# LED_kocka.net
KiCad netlist of a schematic drawn in Altium Designer
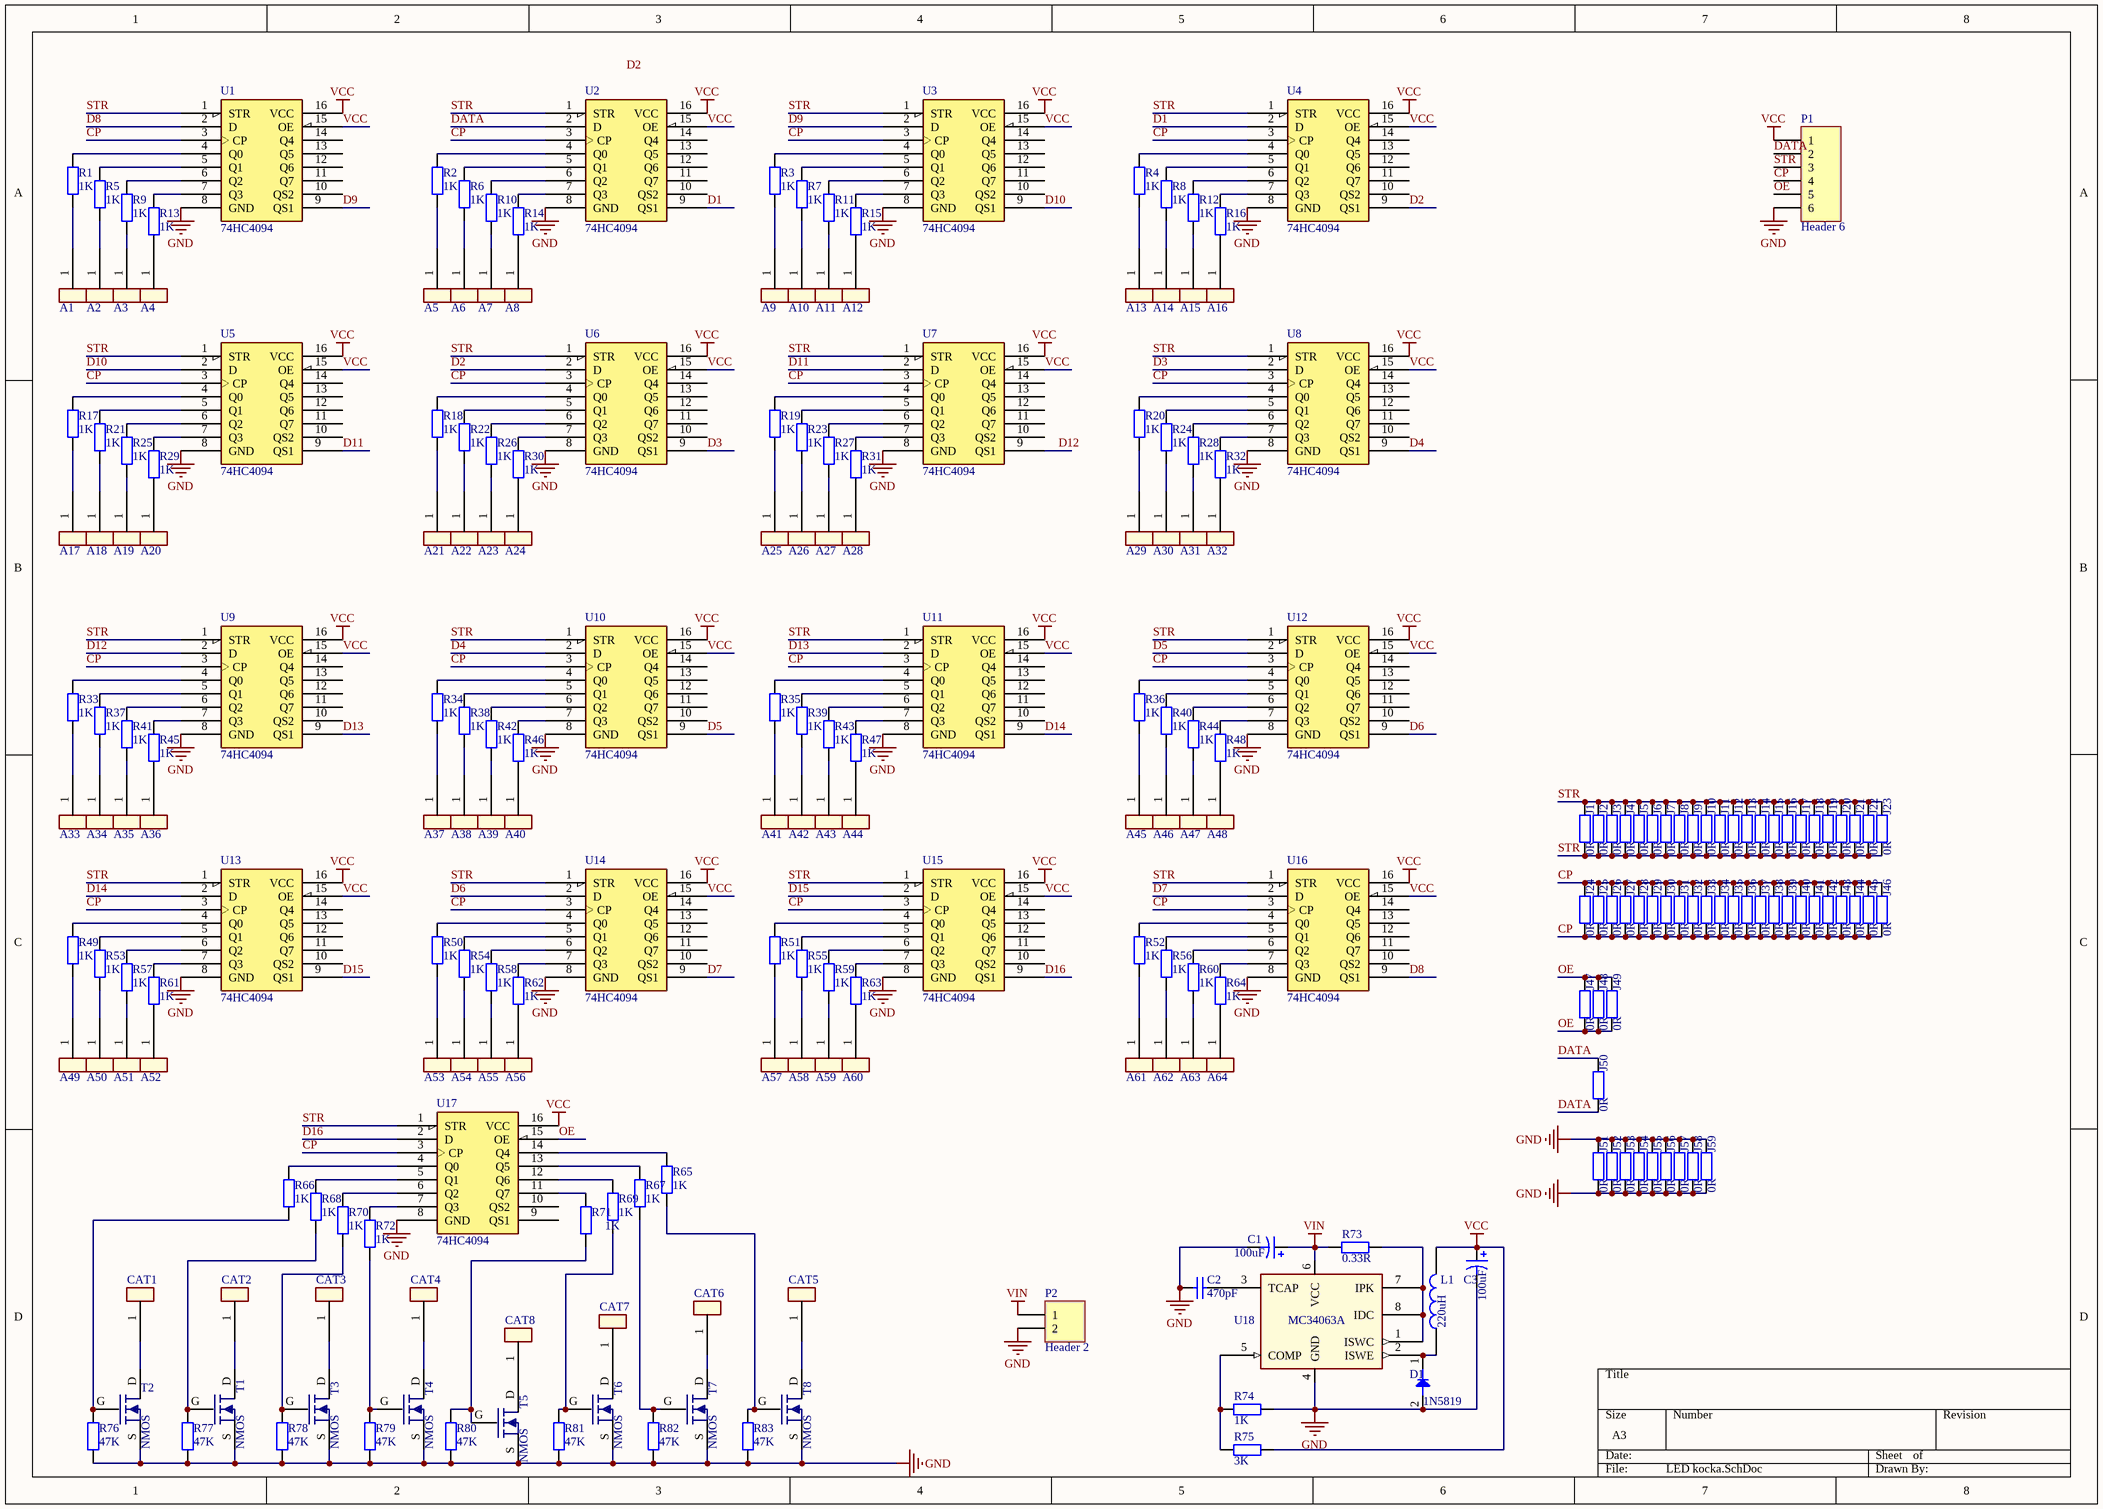
[diagram p0: LED kocka.SchDoc]

(export (version "E")
  (design (tool "Eeschema 10.0.6"))
  (components
    (comp (ref "A1") (value "~") (footprint "via_300x400") (libsource (lib "Other") (part "TestPoint")))
    (comp (ref "A2") (value "~") (footprint "via_300x400") (libsource (lib "Other") (part "TestPoint")))
    (comp (ref "A3") (value "~") (footprint "via_300x400") (libsource (lib "Other") (part "TestPoint")))
    (comp (ref "A4") (value "~") (footprint "via_300x400") (libsource (lib "Other") (part "TestPoint")))
    (comp (ref "A5") (value "~") (footprint "via_300x400") (libsource (lib "Other") (part "TestPoint")))
    (comp (ref "A6") (value "~") (footprint "via_300x400") (libsource (lib "Other") (part "TestPoint")))
    (comp (ref "A7") (value "~") (footprint "via_300x400") (libsource (lib "Other") (part "TestPoint")))
    (comp (ref "A8") (value "~") (footprint "via_300x400") (libsource (lib "Other") (part "TestPoint")))
    (comp (ref "A9") (value "~") (footprint "via_300x400") (libsource (lib "Other") (part "TestPoint")))
    (comp (ref "A10") (value "~") (footprint "via_300x400") (libsource (lib "Other") (part "TestPoint")))
    (comp (ref "A11") (value "~") (footprint "via_300x400") (libsource (lib "Other") (part "TestPoint")))
    (comp (ref "A12") (value "~") (footprint "via_300x400") (libsource (lib "Other") (part "TestPoint")))
    (comp (ref "A13") (value "~") (footprint "via_300x400") (libsource (lib "Other") (part "TestPoint")))
    (comp (ref "A14") (value "~") (footprint "via_300x400") (libsource (lib "Other") (part "TestPoint")))
    (comp (ref "A15") (value "~") (footprint "via_300x400") (libsource (lib "Other") (part "TestPoint")))
    (comp (ref "A16") (value "~") (footprint "via_300x400") (libsource (lib "Other") (part "TestPoint")))
    (comp (ref "A17") (value "~") (footprint "via_300x400") (libsource (lib "Other") (part "TestPoint")))
    (comp (ref "A18") (value "~") (footprint "via_300x400") (libsource (lib "Other") (part "TestPoint")))
    (comp (ref "A19") (value "~") (footprint "via_300x400") (libsource (lib "Other") (part "TestPoint")))
    (comp (ref "A20") (value "~") (footprint "via_300x400") (libsource (lib "Other") (part "TestPoint")))
    (comp (ref "A21") (value "~") (footprint "via_300x400") (libsource (lib "Other") (part "TestPoint")))
    (comp (ref "A22") (value "~") (footprint "via_300x400") (libsource (lib "Other") (part "TestPoint")))
    (comp (ref "A23") (value "~") (footprint "via_300x400") (libsource (lib "Other") (part "TestPoint")))
    (comp (ref "A24") (value "~") (footprint "via_300x400") (libsource (lib "Other") (part "TestPoint")))
    (comp (ref "A25") (value "~") (footprint "via_300x400") (libsource (lib "Other") (part "TestPoint")))
    (comp (ref "A26") (value "~") (footprint "via_300x400") (libsource (lib "Other") (part "TestPoint")))
    (comp (ref "A27") (value "~") (footprint "via_300x400") (libsource (lib "Other") (part "TestPoint")))
    (comp (ref "A28") (value "~") (footprint "via_300x400") (libsource (lib "Other") (part "TestPoint")))
    (comp (ref "A29") (value "~") (footprint "via_300x400") (libsource (lib "Other") (part "TestPoint")))
    (comp (ref "A30") (value "~") (footprint "via_300x400") (libsource (lib "Other") (part "TestPoint")))
    (comp (ref "A31") (value "~") (footprint "via_300x400") (libsource (lib "Other") (part "TestPoint")))
    (comp (ref "A32") (value "~") (footprint "via_300x400") (libsource (lib "Other") (part "TestPoint")))
    (comp (ref "A33") (value "~") (footprint "via_300x400") (libsource (lib "Other") (part "TestPoint")))
    (comp (ref "A34") (value "~") (footprint "via_300x400") (libsource (lib "Other") (part "TestPoint")))
    (comp (ref "A35") (value "~") (footprint "via_300x400") (libsource (lib "Other") (part "TestPoint")))
    (comp (ref "A36") (value "~") (footprint "via_300x400") (libsource (lib "Other") (part "TestPoint")))
    (comp (ref "A37") (value "~") (footprint "via_300x400") (libsource (lib "Other") (part "TestPoint")))
    (comp (ref "A38") (value "~") (footprint "via_300x400") (libsource (lib "Other") (part "TestPoint")))
    (comp (ref "A39") (value "~") (footprint "via_300x400") (libsource (lib "Other") (part "TestPoint")))
    (comp (ref "A40") (value "~") (footprint "via_300x400") (libsource (lib "Other") (part "TestPoint")))
    (comp (ref "A41") (value "~") (footprint "via_300x400") (libsource (lib "Other") (part "TestPoint")))
    (comp (ref "A42") (value "~") (footprint "via_300x400") (libsource (lib "Other") (part "TestPoint")))
    (comp (ref "A43") (value "~") (footprint "via_300x400") (libsource (lib "Other") (part "TestPoint")))
    (comp (ref "A44") (value "~") (footprint "via_300x400") (libsource (lib "Other") (part "TestPoint")))
    (comp (ref "A45") (value "~") (footprint "via_300x400") (libsource (lib "Other") (part "TestPoint")))
    (comp (ref "A46") (value "~") (footprint "via_300x400") (libsource (lib "Other") (part "TestPoint")))
    (comp (ref "A47") (value "~") (footprint "via_300x400") (libsource (lib "Other") (part "TestPoint")))
    (comp (ref "A48") (value "~") (footprint "via_300x400") (libsource (lib "Other") (part "TestPoint")))
    (comp (ref "A49") (value "~") (footprint "via_300x400") (libsource (lib "Other") (part "TestPoint")))
    (comp (ref "A50") (value "~") (footprint "via_300x400") (libsource (lib "Other") (part "TestPoint")))
    (comp (ref "A51") (value "~") (footprint "via_300x400") (libsource (lib "Other") (part "TestPoint")))
    (comp (ref "A52") (value "~") (footprint "via_300x400") (libsource (lib "Other") (part "TestPoint")))
    (comp (ref "A53") (value "~") (footprint "via_300x400") (libsource (lib "Other") (part "TestPoint")))
    (comp (ref "A54") (value "~") (footprint "via_300x400") (libsource (lib "Other") (part "TestPoint")))
    (comp (ref "A55") (value "~") (footprint "via_300x400") (libsource (lib "Other") (part "TestPoint")))
    (comp (ref "A56") (value "~") (footprint "via_300x400") (libsource (lib "Other") (part "TestPoint")))
    (comp (ref "A57") (value "~") (footprint "via_300x400") (libsource (lib "Other") (part "TestPoint")))
    (comp (ref "A58") (value "~") (footprint "via_300x400") (libsource (lib "Other") (part "TestPoint")))
    (comp (ref "A59") (value "~") (footprint "via_300x400") (libsource (lib "Other") (part "TestPoint")))
    (comp (ref "A60") (value "~") (footprint "via_300x400") (libsource (lib "Other") (part "TestPoint")))
    (comp (ref "A61") (value "~") (footprint "via_300x400") (libsource (lib "Other") (part "TestPoint")))
    (comp (ref "A62") (value "~") (footprint "via_300x400") (libsource (lib "Other") (part "TestPoint")))
    (comp (ref "A63") (value "~") (footprint "via_300x400") (libsource (lib "Other") (part "TestPoint")))
    (comp (ref "A64") (value "~") (footprint "via_300x400") (libsource (lib "Other") (part "TestPoint")))
    (comp (ref "C1")
      (value "100uF")
      (footprint "FP_CAP_ELKO_6,3X6,3")
      (description "Polarized Capacitor")
      (libsource (lib "Capacitor") (part "CAP_ELECT"))
    )
    (comp (ref "C2")
      (value "470pF")
      (footprint "FP_0805_CAP_085")
      (description "Capacitor")
      (libsource (lib "Capacitor") (part "CAP"))
    )
    (comp (ref "C3")
      (value "100uF")
      (footprint "FP_CAP_ELKO_6,3X6,3")
      (description "Polarized Capacitor")
      (libsource (lib "Capacitor") (part "CAP_ELECT"))
    )
    (comp (ref "CAT1") (value "~") (footprint "via_300x400") (libsource (lib "") (part "TestPoint_1")))
    (comp (ref "CAT2") (value "~") (footprint "via_300x400") (libsource (lib "") (part "TestPoint_1")))
    (comp (ref "CAT3") (value "~") (footprint "via_300x400") (libsource (lib "") (part "TestPoint_1")))
    (comp (ref "CAT4") (value "~") (footprint "via_300x400") (libsource (lib "") (part "TestPoint_1")))
    (comp (ref "CAT5") (value "~") (footprint "via_300x400") (libsource (lib "") (part "TestPoint_1")))
    (comp (ref "CAT6") (value "~") (footprint "via_300x400") (libsource (lib "") (part "TestPoint_1")))
    (comp (ref "CAT7") (value "~") (footprint "via_300x400") (libsource (lib "") (part "TestPoint_1")))
    (comp (ref "CAT8") (value "~") (footprint "via_300x400") (libsource (lib "") (part "TestPoint_1")))
    (comp (ref "D1") (value "1N5819") (footprint "FP_SOD-123") (libsource (lib "Diode") (part "DIODE")))
    (comp (ref "J1")
      (value "0R")
      (footprint "FP_1206_RES_SIMPLE")
      (description "Resistor")
      (libsource (lib "") (part "RES_1"))
    )
    (comp (ref "J2")
      (value "0R")
      (footprint "FP_1206_RES_SIMPLE")
      (description "Resistor")
      (libsource (lib "") (part "RES_1"))
    )
    (comp (ref "J3")
      (value "0R")
      (footprint "FP_1206_RES_SIMPLE")
      (description "Resistor")
      (libsource (lib "") (part "RES_1"))
    )
    (comp (ref "J4")
      (value "0R")
      (footprint "FP_1206_RES_SIMPLE")
      (description "Resistor")
      (libsource (lib "") (part "RES_1"))
    )
    (comp (ref "J5")
      (value "0R")
      (footprint "FP_1206_RES_SIMPLE")
      (description "Resistor")
      (libsource (lib "") (part "RES_1"))
    )
    (comp (ref "J6")
      (value "0R")
      (footprint "FP_1206_RES_SIMPLE")
      (description "Resistor")
      (libsource (lib "") (part "RES_1"))
    )
    (comp (ref "J7")
      (value "0R")
      (footprint "FP_1206_RES_SIMPLE")
      (description "Resistor")
      (libsource (lib "") (part "RES_1"))
    )
    (comp (ref "J8")
      (value "0R")
      (footprint "FP_1206_RES_SIMPLE")
      (description "Resistor")
      (libsource (lib "") (part "RES_1"))
    )
    (comp (ref "J9")
      (value "0R")
      (footprint "FP_1206_RES_SIMPLE")
      (description "Resistor")
      (libsource (lib "") (part "RES_1"))
    )
    (comp (ref "J10")
      (value "0R")
      (footprint "FP_1206_RES_SIMPLE")
      (description "Resistor")
      (libsource (lib "") (part "RES_1"))
    )
    (comp (ref "J11")
      (value "0R")
      (footprint "FP_1206_RES_SIMPLE")
      (description "Resistor")
      (libsource (lib "") (part "RES_1"))
    )
    (comp (ref "J12")
      (value "0R")
      (footprint "FP_1206_RES_SIMPLE")
      (description "Resistor")
      (libsource (lib "") (part "RES_1"))
    )
    (comp (ref "J13")
      (value "0R")
      (footprint "FP_1206_RES_SIMPLE")
      (description "Resistor")
      (libsource (lib "") (part "RES_1"))
    )
    (comp (ref "J14")
      (value "0R")
      (footprint "FP_1206_RES_SIMPLE")
      (description "Resistor")
      (libsource (lib "") (part "RES_1"))
    )
    (comp (ref "J15")
      (value "0R")
      (footprint "FP_1206_RES_SIMPLE")
      (description "Resistor")
      (libsource (lib "") (part "RES_1"))
    )
    (comp (ref "J16")
      (value "0R")
      (footprint "FP_1206_RES_SIMPLE")
      (description "Resistor")
      (libsource (lib "") (part "RES_1"))
    )
    (comp (ref "J17")
      (value "0R")
      (footprint "FP_1206_RES_SIMPLE")
      (description "Resistor")
      (libsource (lib "") (part "RES_1"))
    )
    (comp (ref "J18")
      (value "0R")
      (footprint "FP_1206_RES_SIMPLE")
      (description "Resistor")
      (libsource (lib "") (part "RES_1"))
    )
    (comp (ref "J19")
      (value "0R")
      (footprint "FP_1206_RES_SIMPLE")
      (description "Resistor")
      (libsource (lib "") (part "RES_1"))
    )
    (comp (ref "J20")
      (value "0R")
      (footprint "FP_1206_RES_SIMPLE")
      (description "Resistor")
      (libsource (lib "") (part "RES_1"))
    )
    (comp (ref "J21")
      (value "0R")
      (footprint "FP_1206_RES_SIMPLE")
      (description "Resistor")
      (libsource (lib "") (part "RES_1"))
    )
    (comp (ref "J22")
      (value "0R")
      (footprint "FP_1206_RES_SIMPLE")
      (description "Resistor")
      (libsource (lib "") (part "RES_1"))
    )
    (comp (ref "J23")
      (value "0R")
      (footprint "FP_1206_RES_SIMPLE")
      (description "Resistor")
      (libsource (lib "") (part "RES_1"))
    )
    (comp (ref "J24")
      (value "0R")
      (footprint "FP_1206_RES_SIMPLE")
      (description "Resistor")
      (libsource (lib "") (part "RES_1"))
    )
    (comp (ref "J25")
      (value "0R")
      (footprint "FP_1206_RES_SIMPLE")
      (description "Resistor")
      (libsource (lib "") (part "RES_1"))
    )
    (comp (ref "J26")
      (value "0R")
      (footprint "FP_1206_RES_SIMPLE")
      (description "Resistor")
      (libsource (lib "") (part "RES_1"))
    )
    (comp (ref "J27")
      (value "0R")
      (footprint "FP_1206_RES_SIMPLE")
      (description "Resistor")
      (libsource (lib "") (part "RES_1"))
    )
    (comp (ref "J28")
      (value "0R")
      (footprint "FP_1206_RES_SIMPLE")
      (description "Resistor")
      (libsource (lib "") (part "RES_1"))
    )
    (comp (ref "J29")
      (value "0R")
      (footprint "FP_1206_RES_SIMPLE")
      (description "Resistor")
      (libsource (lib "") (part "RES_1"))
    )
    (comp (ref "J30")
      (value "0R")
      (footprint "FP_1206_RES_SIMPLE")
      (description "Resistor")
      (libsource (lib "") (part "RES_1"))
    )
    (comp (ref "J31")
      (value "0R")
      (footprint "FP_1206_RES_SIMPLE")
      (description "Resistor")
      (libsource (lib "") (part "RES_1"))
    )
    (comp (ref "J32")
      (value "0R")
      (footprint "FP_1206_RES_SIMPLE")
      (description "Resistor")
      (libsource (lib "") (part "RES_1"))
    )
    (comp (ref "J33")
      (value "0R")
      (footprint "FP_1206_RES_SIMPLE")
      (description "Resistor")
      (libsource (lib "") (part "RES_1"))
    )
    (comp (ref "J34")
      (value "0R")
      (footprint "FP_1206_RES_SIMPLE")
      (description "Resistor")
      (libsource (lib "") (part "RES_1"))
    )
    (comp (ref "J35")
      (value "0R")
      (footprint "FP_1206_RES_SIMPLE")
      (description "Resistor")
      (libsource (lib "") (part "RES_1"))
    )
    (comp (ref "J36")
      (value "0R")
      (footprint "FP_1206_RES_SIMPLE")
      (description "Resistor")
      (libsource (lib "") (part "RES_1"))
    )
    (comp (ref "J37")
      (value "0R")
      (footprint "FP_1206_RES_SIMPLE")
      (description "Resistor")
      (libsource (lib "") (part "RES_1"))
    )
    (comp (ref "J38")
      (value "0R")
      (footprint "FP_1206_RES_SIMPLE")
      (description "Resistor")
      (libsource (lib "") (part "RES_1"))
    )
    (comp (ref "J39")
      (value "0R")
      (footprint "FP_1206_RES_SIMPLE")
      (description "Resistor")
      (libsource (lib "") (part "RES_1"))
    )
    (comp (ref "J40")
      (value "0R")
      (footprint "FP_1206_RES_SIMPLE")
      (description "Resistor")
      (libsource (lib "") (part "RES_1"))
    )
    (comp (ref "J41")
      (value "0R")
      (footprint "FP_1206_RES_SIMPLE")
      (description "Resistor")
      (libsource (lib "") (part "RES_1"))
    )
    (comp (ref "J42")
      (value "0R")
      (footprint "FP_1206_RES_SIMPLE")
      (description "Resistor")
      (libsource (lib "") (part "RES_1"))
    )
    (comp (ref "J43")
      (value "0R")
      (footprint "FP_1206_RES_SIMPLE")
      (description "Resistor")
      (libsource (lib "") (part "RES_1"))
    )
    (comp (ref "J44")
      (value "0R")
      (footprint "FP_1206_RES_SIMPLE")
      (description "Resistor")
      (libsource (lib "") (part "RES_1"))
    )
    (comp (ref "J45")
      (value "0R")
      (footprint "FP_1206_RES_SIMPLE")
      (description "Resistor")
      (libsource (lib "") (part "RES_1"))
    )
    (comp (ref "J46")
      (value "0R")
      (footprint "FP_1206_RES_SIMPLE")
      (description "Resistor")
      (libsource (lib "") (part "RES_1"))
    )
    (comp (ref "J47")
      (value "0R")
      (footprint "FP_1206_RES_SIMPLE")
      (description "Resistor")
      (libsource (lib "") (part "RES_1"))
    )
    (comp (ref "J48")
      (value "0R")
      (footprint "FP_1206_RES_SIMPLE")
      (description "Resistor")
      (libsource (lib "") (part "RES_1"))
    )
    (comp (ref "J49")
      (value "0R")
      (footprint "FP_1206_RES_SIMPLE")
      (description "Resistor")
      (libsource (lib "") (part "RES_1"))
    )
    (comp (ref "J50")
      (value "0R")
      (footprint "FP_1206_RES_SIMPLE")
      (description "Resistor")
      (libsource (lib "") (part "RES_1"))
    )
    (comp (ref "J51")
      (value "0R")
      (footprint "FP_1206_RES_SIMPLE")
      (description "Resistor")
      (libsource (lib "") (part "RES_1"))
    )
    (comp (ref "J52")
      (value "0R")
      (footprint "FP_1206_RES_SIMPLE")
      (description "Resistor")
      (libsource (lib "") (part "RES_1"))
    )
    (comp (ref "J53")
      (value "0R")
      (footprint "FP_1206_RES_SIMPLE")
      (description "Resistor")
      (libsource (lib "") (part "RES_1"))
    )
    (comp (ref "J54")
      (value "0R")
      (footprint "FP_1206_RES_SIMPLE")
      (description "Resistor")
      (libsource (lib "") (part "RES_1"))
    )
    (comp (ref "J55")
      (value "0R")
      (footprint "FP_1206_RES_SIMPLE")
      (description "Resistor")
      (libsource (lib "") (part "RES_1"))
    )
    (comp (ref "J56")
      (value "0R")
      (footprint "FP_1206_RES_SIMPLE")
      (description "Resistor")
      (libsource (lib "") (part "RES_1"))
    )
    (comp (ref "J57")
      (value "0R")
      (footprint "FP_1206_RES_SIMPLE")
      (description "Resistor")
      (libsource (lib "") (part "RES_1"))
    )
    (comp (ref "J58")
      (value "0R")
      (footprint "FP_1206_RES_SIMPLE")
      (description "Resistor")
      (libsource (lib "") (part "RES_1"))
    )
    (comp (ref "J59")
      (value "0R")
      (footprint "FP_1206_RES_SIMPLE")
      (description "Resistor")
      (libsource (lib "") (part "RES_1"))
    )
    (comp (ref "L1")
      (value "220uH")
      (footprint "FP_IND_MURATA3131")
      (description "Inductor")
      (libsource (lib "Inductor") (part "IND"))
    )
    (comp (ref "P1")
      (value "Header 6")
      (footprint "HDR1X6")
      (description "Header, 6-Pin")
      (fields (field (name "PUBLISHER") "Altium Limited"))
      (libsource (lib "Miscellaneous Connectors") (part "Header 6"))
    )
    (comp (ref "P2")
      (value "Header 2")
      (footprint "FP_DC_TAP_ANYA")
      (description "Header, 2-Pin")
      (fields (field (name "PUBLISHER") "Altium Limited"))
      (libsource (lib "Miscellaneous Connectors") (part "Header 2"))
    )
    (comp (ref "R1")
      (value "1K")
      (footprint "FP_0603_RES")
      (description "Resistor")
      (libsource (lib "") (part "RES_1"))
    )
    (comp (ref "R2")
      (value "1K")
      (footprint "FP_0603_RES")
      (description "Resistor")
      (libsource (lib "") (part "RES_1"))
    )
    (comp (ref "R3")
      (value "1K")
      (footprint "FP_0603_RES")
      (description "Resistor")
      (libsource (lib "") (part "RES_1"))
    )
    (comp (ref "R4")
      (value "1K")
      (footprint "FP_0603_RES")
      (description "Resistor")
      (libsource (lib "") (part "RES_1"))
    )
    (comp (ref "R5")
      (value "1K")
      (footprint "FP_0603_RES")
      (description "Resistor")
      (libsource (lib "") (part "RES_1"))
    )
    (comp (ref "R6")
      (value "1K")
      (footprint "FP_0603_RES")
      (description "Resistor")
      (libsource (lib "") (part "RES_1"))
    )
    (comp (ref "R7")
      (value "1K")
      (footprint "FP_0603_RES")
      (description "Resistor")
      (libsource (lib "") (part "RES_1"))
    )
    (comp (ref "R8")
      (value "1K")
      (footprint "FP_0603_RES")
      (description "Resistor")
      (libsource (lib "") (part "RES_1"))
    )
    (comp (ref "R9")
      (value "1K")
      (footprint "FP_0603_RES")
      (description "Resistor")
      (libsource (lib "") (part "RES_1"))
    )
    (comp (ref "R10")
      (value "1K")
      (footprint "FP_0603_RES")
      (description "Resistor")
      (libsource (lib "") (part "RES_1"))
    )
    (comp (ref "R11")
      (value "1K")
      (footprint "FP_0603_RES")
      (description "Resistor")
      (libsource (lib "") (part "RES_1"))
    )
    (comp (ref "R12")
      (value "1K")
      (footprint "FP_0603_RES")
      (description "Resistor")
      (libsource (lib "") (part "RES_1"))
    )
    (comp (ref "R13")
      (value "1K")
      (footprint "FP_0603_RES")
      (description "Resistor")
      (libsource (lib "") (part "RES_1"))
    )
    (comp (ref "R14")
      (value "1K")
      (footprint "FP_0603_RES")
      (description "Resistor")
      (libsource (lib "") (part "RES_1"))
    )
    (comp (ref "R15")
      (value "1K")
      (footprint "FP_0603_RES")
      (description "Resistor")
      (libsource (lib "") (part "RES_1"))
    )
    (comp (ref "R16")
      (value "1K")
      (footprint "FP_0603_RES")
      (description "Resistor")
      (libsource (lib "") (part "RES_1"))
    )
    (comp (ref "R17")
      (value "1K")
      (footprint "FP_0603_RES")
      (description "Resistor")
      (libsource (lib "") (part "RES_1"))
    )
    (comp (ref "R18")
      (value "1K")
      (footprint "FP_0603_RES")
      (description "Resistor")
      (libsource (lib "") (part "RES_1"))
    )
    (comp (ref "R19")
      (value "1K")
      (footprint "FP_0603_RES")
      (description "Resistor")
      (libsource (lib "") (part "RES_1"))
    )
    (comp (ref "R20")
      (value "1K")
      (footprint "FP_0603_RES")
      (description "Resistor")
      (libsource (lib "") (part "RES_1"))
    )
    (comp (ref "R21")
      (value "1K")
      (footprint "FP_0603_RES")
      (description "Resistor")
      (libsource (lib "") (part "RES_1"))
    )
    (comp (ref "R22")
      (value "1K")
      (footprint "FP_0603_RES")
      (description "Resistor")
      (libsource (lib "") (part "RES_1"))
    )
    (comp (ref "R23")
      (value "1K")
      (footprint "FP_0603_RES")
      (description "Resistor")
      (libsource (lib "") (part "RES_1"))
    )
    (comp (ref "R24")
      (value "1K")
      (footprint "FP_0603_RES")
      (description "Resistor")
      (libsource (lib "") (part "RES_1"))
    )
    (comp (ref "R25")
      (value "1K")
      (footprint "FP_0603_RES")
      (description "Resistor")
      (libsource (lib "") (part "RES_1"))
    )
    (comp (ref "R26")
      (value "1K")
      (footprint "FP_0603_RES")
      (description "Resistor")
      (libsource (lib "") (part "RES_1"))
    )
    (comp (ref "R27")
      (value "1K")
      (footprint "FP_0603_RES")
      (description "Resistor")
      (libsource (lib "") (part "RES_1"))
    )
    (comp (ref "R28")
      (value "1K")
      (footprint "FP_0603_RES")
      (description "Resistor")
      (libsource (lib "") (part "RES_1"))
    )
    (comp (ref "R29")
      (value "1K")
      (footprint "FP_0603_RES")
      (description "Resistor")
      (libsource (lib "") (part "RES_1"))
    )
    (comp (ref "R30")
      (value "1K")
      (footprint "FP_0603_RES")
      (description "Resistor")
      (libsource (lib "") (part "RES_1"))
    )
    (comp (ref "R31")
      (value "1K")
      (footprint "FP_0603_RES")
      (description "Resistor")
      (libsource (lib "") (part "RES_1"))
    )
    (comp (ref "R32")
      (value "1K")
      (footprint "FP_0603_RES")
      (description "Resistor")
      (libsource (lib "") (part "RES_1"))
    )
    (comp (ref "R33")
      (value "1K")
      (footprint "FP_0603_RES")
      (description "Resistor")
      (libsource (lib "") (part "RES_1"))
    )
    (comp (ref "R34")
      (value "1K")
      (footprint "FP_0603_RES")
      (description "Resistor")
      (libsource (lib "") (part "RES_1"))
    )
    (comp (ref "R35")
      (value "1K")
      (footprint "FP_0603_RES")
      (description "Resistor")
      (libsource (lib "") (part "RES_1"))
    )
    (comp (ref "R36")
      (value "1K")
      (footprint "FP_0603_RES")
      (description "Resistor")
      (libsource (lib "") (part "RES_1"))
    )
    (comp (ref "R37")
      (value "1K")
      (footprint "FP_0603_RES")
      (description "Resistor")
      (libsource (lib "") (part "RES_1"))
    )
    (comp (ref "R38")
      (value "1K")
      (footprint "FP_0603_RES")
      (description "Resistor")
      (libsource (lib "") (part "RES_1"))
    )
    (comp (ref "R39")
      (value "1K")
      (footprint "FP_0603_RES")
      (description "Resistor")
      (libsource (lib "") (part "RES_1"))
    )
    (comp (ref "R40")
      (value "1K")
      (footprint "FP_0603_RES")
      (description "Resistor")
      (libsource (lib "") (part "RES_1"))
    )
    (comp (ref "R41")
      (value "1K")
      (footprint "FP_0603_RES")
      (description "Resistor")
      (libsource (lib "") (part "RES_1"))
    )
    (comp (ref "R42")
      (value "1K")
      (footprint "FP_0603_RES")
      (description "Resistor")
      (libsource (lib "") (part "RES_1"))
    )
    (comp (ref "R43")
      (value "1K")
      (footprint "FP_0603_RES")
      (description "Resistor")
      (libsource (lib "") (part "RES_1"))
    )
    (comp (ref "R44")
      (value "1K")
      (footprint "FP_0603_RES")
      (description "Resistor")
      (libsource (lib "") (part "RES_1"))
    )
    (comp (ref "R45")
      (value "1K")
      (footprint "FP_0603_RES")
      (description "Resistor")
      (libsource (lib "") (part "RES_1"))
    )
    (comp (ref "R46")
      (value "1K")
      (footprint "FP_0603_RES")
      (description "Resistor")
      (libsource (lib "") (part "RES_1"))
    )
    (comp (ref "R47")
      (value "1K")
      (footprint "FP_0603_RES")
      (description "Resistor")
      (libsource (lib "") (part "RES_1"))
    )
    (comp (ref "R48")
      (value "1K")
      (footprint "FP_0603_RES")
      (description "Resistor")
      (libsource (lib "") (part "RES_1"))
    )
    (comp (ref "R49")
      (value "1K")
      (footprint "FP_0603_RES")
      (description "Resistor")
      (libsource (lib "") (part "RES_1"))
    )
    (comp (ref "R50")
      (value "1K")
      (footprint "FP_0603_RES")
      (description "Resistor")
      (libsource (lib "") (part "RES_1"))
    )
    (comp (ref "R51")
      (value "1K")
      (footprint "FP_0603_RES")
      (description "Resistor")
      (libsource (lib "") (part "RES_1"))
    )
    (comp (ref "R52")
      (value "1K")
      (footprint "FP_0603_RES")
      (description "Resistor")
      (libsource (lib "") (part "RES_1"))
    )
    (comp (ref "R53")
      (value "1K")
      (footprint "FP_0603_RES")
      (description "Resistor")
      (libsource (lib "") (part "RES_1"))
    )
    (comp (ref "R54")
      (value "1K")
      (footprint "FP_0603_RES")
      (description "Resistor")
      (libsource (lib "") (part "RES_1"))
    )
    (comp (ref "R55")
      (value "1K")
      (footprint "FP_0603_RES")
      (description "Resistor")
      (libsource (lib "") (part "RES_1"))
    )
    (comp (ref "R56")
      (value "1K")
      (footprint "FP_0603_RES")
      (description "Resistor")
      (libsource (lib "") (part "RES_1"))
    )
    (comp (ref "R57")
      (value "1K")
      (footprint "FP_0603_RES")
      (description "Resistor")
      (libsource (lib "") (part "RES_1"))
    )
    (comp (ref "R58")
      (value "1K")
      (footprint "FP_0603_RES")
      (description "Resistor")
      (libsource (lib "") (part "RES_1"))
    )
    (comp (ref "R59")
      (value "1K")
      (footprint "FP_0603_RES")
      (description "Resistor")
      (libsource (lib "") (part "RES_1"))
    )
    (comp (ref "R60")
      (value "1K")
      (footprint "FP_0603_RES")
      (description "Resistor")
      (libsource (lib "") (part "RES_1"))
    )
    (comp (ref "R61")
      (value "1K")
      (footprint "FP_0603_RES")
      (description "Resistor")
      (libsource (lib "") (part "RES_1"))
    )
    (comp (ref "R62")
      (value "1K")
      (footprint "FP_0603_RES")
      (description "Resistor")
      (libsource (lib "") (part "RES_1"))
    )
    (comp (ref "R63")
      (value "1K")
      (footprint "FP_0603_RES")
      (description "Resistor")
      (libsource (lib "") (part "RES_1"))
    )
    (comp (ref "R64")
      (value "1K")
      (footprint "FP_0603_RES")
      (description "Resistor")
      (libsource (lib "") (part "RES_1"))
    )
    (comp (ref "R65")
      (value "1K")
      (footprint "FP_0603_RES")
      (description "Resistor")
      (libsource (lib "Resistor") (part "RES"))
    )
    (comp (ref "R66")
      (value "1K")
      (footprint "FP_0603_RES")
      (description "Resistor")
      (libsource (lib "") (part "RES_1"))
    )
    (comp (ref "R67")
      (value "1K")
      (footprint "FP_0603_RES")
      (description "Resistor")
      (libsource (lib "Resistor") (part "RES"))
    )
    (comp (ref "R68")
      (value "1K")
      (footprint "FP_0603_RES")
      (description "Resistor")
      (libsource (lib "") (part "RES_1"))
    )
    (comp (ref "R69")
      (value "1K")
      (footprint "FP_0603_RES")
      (description "Resistor")
      (libsource (lib "Resistor") (part "RES"))
    )
    (comp (ref "R70")
      (value "1K")
      (footprint "FP_0603_RES")
      (description "Resistor")
      (libsource (lib "") (part "RES_1"))
    )
    (comp (ref "R71")
      (value "1K")
      (footprint "FP_0603_RES")
      (description "Resistor")
      (libsource (lib "Resistor") (part "RES"))
    )
    (comp (ref "R72")
      (value "1K")
      (footprint "FP_0603_RES")
      (description "Resistor")
      (libsource (lib "") (part "RES_1"))
    )
    (comp (ref "R73")
      (value "0.33R")
      (footprint "FP_0805_RES")
      (description "Resistor")
      (libsource (lib "Resistor") (part "RES"))
    )
    (comp (ref "R74")
      (value "1K")
      (footprint "FP_0805_RES")
      (description "Resistor")
      (libsource (lib "Resistor") (part "RES"))
    )
    (comp (ref "R75")
      (value "3K")
      (footprint "FP_0805_RES")
      (description "Resistor")
      (libsource (lib "Resistor") (part "RES"))
    )
    (comp (ref "R76")
      (value "47K")
      (footprint "FP_0603_RES")
      (description "Resistor")
      (libsource (lib "") (part "RES_2"))
    )
    (comp (ref "R77")
      (value "47K")
      (footprint "FP_0603_RES")
      (description "Resistor")
      (libsource (lib "") (part "RES_2"))
    )
    (comp (ref "R78")
      (value "47K")
      (footprint "FP_0603_RES")
      (description "Resistor")
      (libsource (lib "") (part "RES_2"))
    )
    (comp (ref "R79")
      (value "47K")
      (footprint "FP_0603_RES")
      (description "Resistor")
      (libsource (lib "") (part "RES_2"))
    )
    (comp (ref "R80")
      (value "47K")
      (footprint "FP_0603_RES")
      (description "Resistor")
      (libsource (lib "") (part "RES_2"))
    )
    (comp (ref "R81")
      (value "47K")
      (footprint "FP_0603_RES")
      (description "Resistor")
      (libsource (lib "") (part "RES_2"))
    )
    (comp (ref "R82")
      (value "47K")
      (footprint "FP_0603_RES")
      (description "Resistor")
      (libsource (lib "") (part "RES_2"))
    )
    (comp (ref "R83")
      (value "47K")
      (footprint "FP_0603_RES")
      (description "Resistor")
      (libsource (lib "") (part "RES_1"))
    )
    (comp (ref "T1") (value "NMOS") (footprint "BBMF170") (libsource (lib "FET") (part "NMOS")))
    (comp (ref "T2") (value "NMOS") (footprint "BBMF170") (libsource (lib "FET") (part "NMOS")))
    (comp (ref "T3") (value "NMOS") (footprint "BBMF170") (libsource (lib "FET") (part "NMOS")))
    (comp (ref "T4") (value "NMOS") (footprint "BBMF170") (libsource (lib "FET") (part "NMOS")))
    (comp (ref "T5") (value "NMOS") (footprint "BBMF170") (libsource (lib "FET") (part "NMOS")))
    (comp (ref "T6") (value "NMOS") (footprint "BBMF170") (libsource (lib "FET") (part "NMOS")))
    (comp (ref "T7") (value "NMOS") (footprint "BBMF170") (libsource (lib "FET") (part "NMOS")))
    (comp (ref "T8") (value "NMOS") (footprint "BBMF170") (libsource (lib "FET") (part "NMOS")))
    (comp (ref "U1")
      (value "74HC4094")
      (footprint "SOIC16")
      (description "shift reg")
      (libsource (lib "Digital") (part "74HC4094"))
    )
    (comp (ref "U2")
      (value "74HC4094")
      (footprint "SOIC16")
      (description "shift reg")
      (libsource (lib "Digital") (part "74HC4094"))
    )
    (comp (ref "U3")
      (value "74HC4094")
      (footprint "SOIC16")
      (description "shift reg")
      (libsource (lib "Digital") (part "74HC4094"))
    )
    (comp (ref "U4")
      (value "74HC4094")
      (footprint "SOIC16")
      (description "shift reg")
      (libsource (lib "Digital") (part "74HC4094"))
    )
    (comp (ref "U5")
      (value "74HC4094")
      (footprint "SOIC16")
      (description "shift reg")
      (libsource (lib "Digital") (part "74HC4094"))
    )
    (comp (ref "U6")
      (value "74HC4094")
      (footprint "SOIC16")
      (description "shift reg")
      (libsource (lib "Digital") (part "74HC4094"))
    )
    (comp (ref "U7")
      (value "74HC4094")
      (footprint "SOIC16")
      (description "shift reg")
      (libsource (lib "Digital") (part "74HC4094"))
    )
    (comp (ref "U8")
      (value "74HC4094")
      (footprint "SOIC16")
      (description "shift reg")
      (libsource (lib "Digital") (part "74HC4094"))
    )
    (comp (ref "U9")
      (value "74HC4094")
      (footprint "SOIC16")
      (description "shift reg")
      (libsource (lib "Digital") (part "74HC4094"))
    )
    (comp (ref "U10")
      (value "74HC4094")
      (footprint "SOIC16")
      (description "shift reg")
      (libsource (lib "Digital") (part "74HC4094"))
    )
    (comp (ref "U11")
      (value "74HC4094")
      (footprint "SOIC16")
      (description "shift reg")
      (libsource (lib "Digital") (part "74HC4094"))
    )
    (comp (ref "U12")
      (value "74HC4094")
      (footprint "SOIC16")
      (description "shift reg")
      (libsource (lib "Digital") (part "74HC4094"))
    )
    (comp (ref "U13")
      (value "74HC4094")
      (footprint "SOIC16")
      (description "shift reg")
      (libsource (lib "Digital") (part "74HC4094"))
    )
    (comp (ref "U14")
      (value "74HC4094")
      (footprint "SOIC16")
      (description "shift reg")
      (libsource (lib "Digital") (part "74HC4094"))
    )
    (comp (ref "U15")
      (value "74HC4094")
      (footprint "SOIC16")
      (description "shift reg")
      (libsource (lib "Digital") (part "74HC4094"))
    )
    (comp (ref "U16")
      (value "74HC4094")
      (footprint "SOIC16")
      (description "shift reg")
      (libsource (lib "Digital") (part "74HC4094"))
    )
    (comp (ref "U17")
      (value "74HC4094")
      (footprint "SOIC16")
      (description "shift reg")
      (libsource (lib "Digital") (part "74HC4094"))
    )
    (comp (ref "U18")
      (value "MC34063A")
      (footprint "FP_SO8_MS012AA")
      (libsource (lib "Supply") (part "MC34063A"))
    )
  )
  (nets
    (net (code "1") (name "/CP") (class "Default")
      (node (ref "J24") (pin "1") (pinfunction "1_1") (pintype "passive"))
      (node (ref "J24") (pin "2") (pinfunction "2_2") (pintype "passive"))
      (node (ref "J25") (pin "1") (pinfunction "1_1") (pintype "passive"))
      (node (ref "J25") (pin "2") (pinfunction "2_2") (pintype "passive"))
      (node (ref "J26") (pin "1") (pinfunction "1_1") (pintype "passive"))
      (node (ref "J26") (pin "2") (pinfunction "2_2") (pintype "passive"))
      (node (ref "J27") (pin "1") (pinfunction "1_1") (pintype "passive"))
      (node (ref "J27") (pin "2") (pinfunction "2_2") (pintype "passive"))
      (node (ref "J28") (pin "1") (pinfunction "1_1") (pintype "passive"))
      (node (ref "J28") (pin "2") (pinfunction "2_2") (pintype "passive"))
      (node (ref "J29") (pin "1") (pinfunction "1_1") (pintype "passive"))
      (node (ref "J29") (pin "2") (pinfunction "2_2") (pintype "passive"))
      (node (ref "J30") (pin "1") (pinfunction "1_1") (pintype "passive"))
      (node (ref "J30") (pin "2") (pinfunction "2_2") (pintype "passive"))
      (node (ref "J31") (pin "1") (pinfunction "1_1") (pintype "passive"))
      (node (ref "J31") (pin "2") (pinfunction "2_2") (pintype "passive"))
      (node (ref "J32") (pin "1") (pinfunction "1_1") (pintype "passive"))
      (node (ref "J32") (pin "2") (pinfunction "2_2") (pintype "passive"))
      (node (ref "J33") (pin "1") (pinfunction "1_1") (pintype "passive"))
      (node (ref "J33") (pin "2") (pinfunction "2_2") (pintype "passive"))
      (node (ref "J34") (pin "1") (pinfunction "1_1") (pintype "passive"))
      (node (ref "J34") (pin "2") (pinfunction "2_2") (pintype "passive"))
      (node (ref "J35") (pin "1") (pinfunction "1_1") (pintype "passive"))
      (node (ref "J35") (pin "2") (pinfunction "2_2") (pintype "passive"))
      (node (ref "J36") (pin "1") (pinfunction "1_1") (pintype "passive"))
      (node (ref "J36") (pin "2") (pinfunction "2_2") (pintype "passive"))
      (node (ref "J37") (pin "1") (pinfunction "1_1") (pintype "passive"))
      (node (ref "J37") (pin "2") (pinfunction "2_2") (pintype "passive"))
      (node (ref "J38") (pin "1") (pinfunction "1_1") (pintype "passive"))
      (node (ref "J38") (pin "2") (pinfunction "2_2") (pintype "passive"))
      (node (ref "J39") (pin "1") (pinfunction "1_1") (pintype "passive"))
      (node (ref "J39") (pin "2") (pinfunction "2_2") (pintype "passive"))
      (node (ref "J40") (pin "1") (pinfunction "1_1") (pintype "passive"))
      (node (ref "J40") (pin "2") (pinfunction "2_2") (pintype "passive"))
      (node (ref "J41") (pin "1") (pinfunction "1_1") (pintype "passive"))
      (node (ref "J41") (pin "2") (pinfunction "2_2") (pintype "passive"))
      (node (ref "J42") (pin "1") (pinfunction "1_1") (pintype "passive"))
      (node (ref "J42") (pin "2") (pinfunction "2_2") (pintype "passive"))
      (node (ref "J43") (pin "1") (pinfunction "1_1") (pintype "passive"))
      (node (ref "J43") (pin "2") (pinfunction "2_2") (pintype "passive"))
      (node (ref "J44") (pin "1") (pinfunction "1_1") (pintype "passive"))
      (node (ref "J44") (pin "2") (pinfunction "2_2") (pintype "passive"))
      (node (ref "J45") (pin "1") (pinfunction "1_1") (pintype "passive"))
      (node (ref "J45") (pin "2") (pinfunction "2_2") (pintype "passive"))
      (node (ref "J46") (pin "1") (pinfunction "1_1") (pintype "passive"))
      (node (ref "J46") (pin "2") (pinfunction "2_2") (pintype "passive"))
      (node (ref "P1") (pin "4") (pinfunction "4_4") (pintype "passive"))
      (node (ref "U1") (pin "3") (pinfunction "CP_3") (pintype "passive"))
      (node (ref "U10") (pin "3") (pinfunction "CP_3") (pintype "passive"))
      (node (ref "U11") (pin "3") (pinfunction "CP_3") (pintype "passive"))
      (node (ref "U12") (pin "3") (pinfunction "CP_3") (pintype "passive"))
      (node (ref "U13") (pin "3") (pinfunction "CP_3") (pintype "passive"))
      (node (ref "U14") (pin "3") (pinfunction "CP_3") (pintype "passive"))
      (node (ref "U15") (pin "3") (pinfunction "CP_3") (pintype "passive"))
      (node (ref "U16") (pin "3") (pinfunction "CP_3") (pintype "passive"))
      (node (ref "U17") (pin "3") (pinfunction "CP_3") (pintype "passive"))
      (node (ref "U2") (pin "3") (pinfunction "CP_3") (pintype "passive"))
      (node (ref "U3") (pin "3") (pinfunction "CP_3") (pintype "passive"))
      (node (ref "U4") (pin "3") (pinfunction "CP_3") (pintype "passive"))
      (node (ref "U5") (pin "3") (pinfunction "CP_3") (pintype "passive"))
      (node (ref "U6") (pin "3") (pinfunction "CP_3") (pintype "passive"))
      (node (ref "U7") (pin "3") (pinfunction "CP_3") (pintype "passive"))
      (node (ref "U8") (pin "3") (pinfunction "CP_3") (pintype "passive"))
      (node (ref "U9") (pin "3") (pinfunction "CP_3") (pintype "passive"))
    )
    (net (code "2") (name "/D1") (class "Default")
      (node (ref "U2") (pin "9") (pinfunction "QS1_9") (pintype "passive"))
      (node (ref "U4") (pin "2") (pinfunction "D_2") (pintype "passive"))
    )
    (net (code "3") (name "/D2") (class "Default")
      (node (ref "U4") (pin "9") (pinfunction "QS1_9") (pintype "passive"))
      (node (ref "U6") (pin "2") (pinfunction "D_2") (pintype "passive"))
    )
    (net (code "4") (name "/D3") (class "Default")
      (node (ref "U6") (pin "9") (pinfunction "QS1_9") (pintype "passive"))
      (node (ref "U8") (pin "2") (pinfunction "D_2") (pintype "passive"))
    )
    (net (code "5") (name "/D4") (class "Default")
      (node (ref "U10") (pin "2") (pinfunction "D_2") (pintype "passive"))
      (node (ref "U8") (pin "9") (pinfunction "QS1_9") (pintype "passive"))
    )
    (net (code "6") (name "/D5") (class "Default")
      (node (ref "U10") (pin "9") (pinfunction "QS1_9") (pintype "passive"))
      (node (ref "U12") (pin "2") (pinfunction "D_2") (pintype "passive"))
    )
    (net (code "7") (name "/D6") (class "Default")
      (node (ref "U12") (pin "9") (pinfunction "QS1_9") (pintype "passive"))
      (node (ref "U14") (pin "2") (pinfunction "D_2") (pintype "passive"))
    )
    (net (code "8") (name "/D7") (class "Default")
      (node (ref "U14") (pin "9") (pinfunction "QS1_9") (pintype "passive"))
      (node (ref "U16") (pin "2") (pinfunction "D_2") (pintype "passive"))
    )
    (net (code "9") (name "/D8") (class "Default")
      (node (ref "U1") (pin "2") (pinfunction "D_2") (pintype "passive"))
      (node (ref "U16") (pin "9") (pinfunction "QS1_9") (pintype "passive"))
    )
    (net (code "10") (name "/D9") (class "Default")
      (node (ref "U1") (pin "9") (pinfunction "QS1_9") (pintype "passive"))
      (node (ref "U3") (pin "2") (pinfunction "D_2") (pintype "passive"))
    )
    (net (code "11") (name "/D10") (class "Default")
      (node (ref "U3") (pin "9") (pinfunction "QS1_9") (pintype "passive"))
      (node (ref "U5") (pin "2") (pinfunction "D_2") (pintype "passive"))
    )
    (net (code "12") (name "/D11") (class "Default")
      (node (ref "U5") (pin "9") (pinfunction "QS1_9") (pintype "passive"))
      (node (ref "U7") (pin "2") (pinfunction "D_2") (pintype "passive"))
    )
    (net (code "13") (name "/D12") (class "Default")
      (node (ref "U7") (pin "9") (pinfunction "QS1_9") (pintype "passive"))
      (node (ref "U9") (pin "2") (pinfunction "D_2") (pintype "passive"))
    )
    (net (code "14") (name "/D13") (class "Default")
      (node (ref "U11") (pin "2") (pinfunction "D_2") (pintype "passive"))
      (node (ref "U9") (pin "9") (pinfunction "QS1_9") (pintype "passive"))
    )
    (net (code "15") (name "/D14") (class "Default")
      (node (ref "U11") (pin "9") (pinfunction "QS1_9") (pintype "passive"))
      (node (ref "U13") (pin "2") (pinfunction "D_2") (pintype "passive"))
    )
    (net (code "16") (name "/D15") (class "Default")
      (node (ref "U13") (pin "9") (pinfunction "QS1_9") (pintype "passive"))
      (node (ref "U15") (pin "2") (pinfunction "D_2") (pintype "passive"))
    )
    (net (code "17") (name "/D16") (class "Default")
      (node (ref "U15") (pin "9") (pinfunction "QS1_9") (pintype "passive"))
      (node (ref "U17") (pin "2") (pinfunction "D_2") (pintype "passive"))
    )
    (net (code "18") (name "/DATA") (class "Default")
      (node (ref "J50") (pin "1") (pinfunction "1_1") (pintype "passive"))
      (node (ref "J50") (pin "2") (pinfunction "2_2") (pintype "passive"))
      (node (ref "P1") (pin "2") (pinfunction "2_2") (pintype "passive"))
      (node (ref "U2") (pin "2") (pinfunction "D_2") (pintype "passive"))
    )
    (net (code "19") (name "/OE") (class "Default")
      (node (ref "J47") (pin "1") (pinfunction "1_1") (pintype "passive"))
      (node (ref "J47") (pin "2") (pinfunction "2_2") (pintype "passive"))
      (node (ref "J48") (pin "1") (pinfunction "1_1") (pintype "passive"))
      (node (ref "J48") (pin "2") (pinfunction "2_2") (pintype "passive"))
      (node (ref "J49") (pin "1") (pinfunction "1_1") (pintype "passive"))
      (node (ref "J49") (pin "2") (pinfunction "2_2") (pintype "passive"))
      (node (ref "P1") (pin "5") (pinfunction "5_5") (pintype "passive"))
      (node (ref "U17") (pin "15") (pinfunction "OE_15") (pintype "passive"))
    )
    (net (code "20") (name "/STR") (class "Default")
      (node (ref "J1") (pin "1") (pinfunction "1_1") (pintype "passive"))
      (node (ref "J1") (pin "2") (pinfunction "2_2") (pintype "passive"))
      (node (ref "J10") (pin "1") (pinfunction "1_1") (pintype "passive"))
      (node (ref "J10") (pin "2") (pinfunction "2_2") (pintype "passive"))
      (node (ref "J11") (pin "1") (pinfunction "1_1") (pintype "passive"))
      (node (ref "J11") (pin "2") (pinfunction "2_2") (pintype "passive"))
      (node (ref "J12") (pin "1") (pinfunction "1_1") (pintype "passive"))
      (node (ref "J12") (pin "2") (pinfunction "2_2") (pintype "passive"))
      (node (ref "J13") (pin "1") (pinfunction "1_1") (pintype "passive"))
      (node (ref "J13") (pin "2") (pinfunction "2_2") (pintype "passive"))
      (node (ref "J14") (pin "1") (pinfunction "1_1") (pintype "passive"))
      (node (ref "J14") (pin "2") (pinfunction "2_2") (pintype "passive"))
      (node (ref "J15") (pin "1") (pinfunction "1_1") (pintype "passive"))
      (node (ref "J15") (pin "2") (pinfunction "2_2") (pintype "passive"))
      (node (ref "J16") (pin "1") (pinfunction "1_1") (pintype "passive"))
      (node (ref "J16") (pin "2") (pinfunction "2_2") (pintype "passive"))
      (node (ref "J17") (pin "1") (pinfunction "1_1") (pintype "passive"))
      (node (ref "J17") (pin "2") (pinfunction "2_2") (pintype "passive"))
      (node (ref "J18") (pin "1") (pinfunction "1_1") (pintype "passive"))
      (node (ref "J18") (pin "2") (pinfunction "2_2") (pintype "passive"))
      (node (ref "J19") (pin "1") (pinfunction "1_1") (pintype "passive"))
      (node (ref "J19") (pin "2") (pinfunction "2_2") (pintype "passive"))
      (node (ref "J2") (pin "1") (pinfunction "1_1") (pintype "passive"))
      (node (ref "J2") (pin "2") (pinfunction "2_2") (pintype "passive"))
      (node (ref "J20") (pin "1") (pinfunction "1_1") (pintype "passive"))
      (node (ref "J20") (pin "2") (pinfunction "2_2") (pintype "passive"))
      (node (ref "J21") (pin "1") (pinfunction "1_1") (pintype "passive"))
      (node (ref "J21") (pin "2") (pinfunction "2_2") (pintype "passive"))
      (node (ref "J22") (pin "1") (pinfunction "1_1") (pintype "passive"))
      (node (ref "J22") (pin "2") (pinfunction "2_2") (pintype "passive"))
      (node (ref "J23") (pin "1") (pinfunction "1_1") (pintype "passive"))
      (node (ref "J23") (pin "2") (pinfunction "2_2") (pintype "passive"))
      (node (ref "J3") (pin "1") (pinfunction "1_1") (pintype "passive"))
      (node (ref "J3") (pin "2") (pinfunction "2_2") (pintype "passive"))
      (node (ref "J4") (pin "1") (pinfunction "1_1") (pintype "passive"))
      (node (ref "J4") (pin "2") (pinfunction "2_2") (pintype "passive"))
      (node (ref "J5") (pin "1") (pinfunction "1_1") (pintype "passive"))
      (node (ref "J5") (pin "2") (pinfunction "2_2") (pintype "passive"))
      (node (ref "J6") (pin "1") (pinfunction "1_1") (pintype "passive"))
      (node (ref "J6") (pin "2") (pinfunction "2_2") (pintype "passive"))
      (node (ref "J7") (pin "1") (pinfunction "1_1") (pintype "passive"))
      (node (ref "J7") (pin "2") (pinfunction "2_2") (pintype "passive"))
      (node (ref "J8") (pin "1") (pinfunction "1_1") (pintype "passive"))
      (node (ref "J8") (pin "2") (pinfunction "2_2") (pintype "passive"))
      (node (ref "J9") (pin "1") (pinfunction "1_1") (pintype "passive"))
      (node (ref "J9") (pin "2") (pinfunction "2_2") (pintype "passive"))
      (node (ref "P1") (pin "3") (pinfunction "3_3") (pintype "passive"))
      (node (ref "U1") (pin "1") (pinfunction "STR_1") (pintype "passive"))
      (node (ref "U10") (pin "1") (pinfunction "STR_1") (pintype "passive"))
      (node (ref "U11") (pin "1") (pinfunction "STR_1") (pintype "passive"))
      (node (ref "U12") (pin "1") (pinfunction "STR_1") (pintype "passive"))
      (node (ref "U13") (pin "1") (pinfunction "STR_1") (pintype "passive"))
      (node (ref "U14") (pin "1") (pinfunction "STR_1") (pintype "passive"))
      (node (ref "U15") (pin "1") (pinfunction "STR_1") (pintype "passive"))
      (node (ref "U16") (pin "1") (pinfunction "STR_1") (pintype "passive"))
      (node (ref "U17") (pin "1") (pinfunction "STR_1") (pintype "passive"))
      (node (ref "U2") (pin "1") (pinfunction "STR_1") (pintype "passive"))
      (node (ref "U3") (pin "1") (pinfunction "STR_1") (pintype "passive"))
      (node (ref "U4") (pin "1") (pinfunction "STR_1") (pintype "passive"))
      (node (ref "U5") (pin "1") (pinfunction "STR_1") (pintype "passive"))
      (node (ref "U6") (pin "1") (pinfunction "STR_1") (pintype "passive"))
      (node (ref "U7") (pin "1") (pinfunction "STR_1") (pintype "passive"))
      (node (ref "U8") (pin "1") (pinfunction "STR_1") (pintype "passive"))
      (node (ref "U9") (pin "1") (pinfunction "STR_1") (pintype "passive"))
    )
    (net (code "21") (name "GND") (class "Default")
      (node (ref "C1") (pin "N") (pinfunction "N_N") (pintype "passive"))
      (node (ref "C2") (pin "1") (pinfunction "1_1") (pintype "passive"))
      (node (ref "C3") (pin "N") (pinfunction "N_N") (pintype "passive"))
      (node (ref "D1") (pin "2") (pinfunction "2_2") (pintype "passive"))
      (node (ref "J51") (pin "1") (pinfunction "1_1") (pintype "passive"))
      (node (ref "J51") (pin "2") (pinfunction "2_2") (pintype "passive"))
      (node (ref "J52") (pin "1") (pinfunction "1_1") (pintype "passive"))
      (node (ref "J52") (pin "2") (pinfunction "2_2") (pintype "passive"))
      (node (ref "J53") (pin "1") (pinfunction "1_1") (pintype "passive"))
      (node (ref "J53") (pin "2") (pinfunction "2_2") (pintype "passive"))
      (node (ref "J54") (pin "1") (pinfunction "1_1") (pintype "passive"))
      (node (ref "J54") (pin "2") (pinfunction "2_2") (pintype "passive"))
      (node (ref "J55") (pin "1") (pinfunction "1_1") (pintype "passive"))
      (node (ref "J55") (pin "2") (pinfunction "2_2") (pintype "passive"))
      (node (ref "J56") (pin "1") (pinfunction "1_1") (pintype "passive"))
      (node (ref "J56") (pin "2") (pinfunction "2_2") (pintype "passive"))
      (node (ref "J57") (pin "1") (pinfunction "1_1") (pintype "passive"))
      (node (ref "J57") (pin "2") (pinfunction "2_2") (pintype "passive"))
      (node (ref "J58") (pin "1") (pinfunction "1_1") (pintype "passive"))
      (node (ref "J58") (pin "2") (pinfunction "2_2") (pintype "passive"))
      (node (ref "J59") (pin "1") (pinfunction "1_1") (pintype "passive"))
      (node (ref "J59") (pin "2") (pinfunction "2_2") (pintype "passive"))
      (node (ref "P1") (pin "6") (pinfunction "6_6") (pintype "passive"))
      (node (ref "P2") (pin "2") (pinfunction "2_2") (pintype "passive"))
      (node (ref "R74") (pin "2") (pinfunction "2_2") (pintype "passive"))
      (node (ref "R76") (pin "2") (pinfunction "2_2") (pintype "passive"))
      (node (ref "R77") (pin "2") (pinfunction "2_2") (pintype "passive"))
      (node (ref "R78") (pin "2") (pinfunction "2_2") (pintype "passive"))
      (node (ref "R79") (pin "2") (pinfunction "2_2") (pintype "passive"))
      (node (ref "R80") (pin "2") (pinfunction "2_2") (pintype "passive"))
      (node (ref "R81") (pin "2") (pinfunction "2_2") (pintype "passive"))
      (node (ref "R82") (pin "2") (pinfunction "2_2") (pintype "passive"))
      (node (ref "R83") (pin "1") (pinfunction "1_1") (pintype "passive"))
      (node (ref "T1") (pin "S") (pinfunction "S_S") (pintype "passive"))
      (node (ref "T2") (pin "S") (pinfunction "S_S") (pintype "passive"))
      (node (ref "T3") (pin "S") (pinfunction "S_S") (pintype "passive"))
      (node (ref "T4") (pin "S") (pinfunction "S_S") (pintype "passive"))
      (node (ref "T5") (pin "S") (pinfunction "S_S") (pintype "passive"))
      (node (ref "T6") (pin "S") (pinfunction "S_S") (pintype "passive"))
      (node (ref "T7") (pin "S") (pinfunction "S_S") (pintype "passive"))
      (node (ref "T8") (pin "S") (pinfunction "S_S") (pintype "passive"))
      (node (ref "U1") (pin "8") (pinfunction "GND_8") (pintype "passive"))
      (node (ref "U10") (pin "8") (pinfunction "GND_8") (pintype "passive"))
      (node (ref "U11") (pin "8") (pinfunction "GND_8") (pintype "passive"))
      (node (ref "U12") (pin "8") (pinfunction "GND_8") (pintype "passive"))
      (node (ref "U13") (pin "8") (pinfunction "GND_8") (pintype "passive"))
      (node (ref "U14") (pin "8") (pinfunction "GND_8") (pintype "passive"))
      (node (ref "U15") (pin "8") (pinfunction "GND_8") (pintype "passive"))
      (node (ref "U16") (pin "8") (pinfunction "GND_8") (pintype "passive"))
      (node (ref "U17") (pin "8") (pinfunction "GND_8") (pintype "passive"))
      (node (ref "U18") (pin "4") (pinfunction "GND_4") (pintype "passive"))
      (node (ref "U2") (pin "8") (pinfunction "GND_8") (pintype "passive"))
      (node (ref "U3") (pin "8") (pinfunction "GND_8") (pintype "passive"))
      (node (ref "U4") (pin "8") (pinfunction "GND_8") (pintype "passive"))
      (node (ref "U5") (pin "8") (pinfunction "GND_8") (pintype "passive"))
      (node (ref "U6") (pin "8") (pinfunction "GND_8") (pintype "passive"))
      (node (ref "U7") (pin "8") (pinfunction "GND_8") (pintype "passive"))
      (node (ref "U8") (pin "8") (pinfunction "GND_8") (pintype "passive"))
      (node (ref "U9") (pin "8") (pinfunction "GND_8") (pintype "passive"))
    )
    (net (code "22") (name "Net-(A1-Pad1)") (class "Default")
      (node (ref "A1") (pin "1") (pinfunction "1_1") (pintype "passive"))
      (node (ref "R1") (pin "1") (pinfunction "1_1") (pintype "passive"))
    )
    (net (code "23") (name "Net-(A2-Pad1)") (class "Default")
      (node (ref "A2") (pin "1") (pinfunction "1_1") (pintype "passive"))
      (node (ref "R5") (pin "1") (pinfunction "1_1") (pintype "passive"))
    )
    (net (code "24") (name "Net-(A3-Pad1)") (class "Default")
      (node (ref "A3") (pin "1") (pinfunction "1_1") (pintype "passive"))
      (node (ref "R9") (pin "1") (pinfunction "1_1") (pintype "passive"))
    )
    (net (code "25") (name "Net-(A4-Pad1)") (class "Default")
      (node (ref "A4") (pin "1") (pinfunction "1_1") (pintype "passive"))
      (node (ref "R13") (pin "1") (pinfunction "1_1") (pintype "passive"))
    )
    (net (code "26") (name "Net-(A5-Pad1)") (class "Default")
      (node (ref "A5") (pin "1") (pinfunction "1_1") (pintype "passive"))
      (node (ref "R2") (pin "1") (pinfunction "1_1") (pintype "passive"))
    )
    (net (code "27") (name "Net-(A6-Pad1)") (class "Default")
      (node (ref "A6") (pin "1") (pinfunction "1_1") (pintype "passive"))
      (node (ref "R6") (pin "1") (pinfunction "1_1") (pintype "passive"))
    )
    (net (code "28") (name "Net-(A7-Pad1)") (class "Default")
      (node (ref "A7") (pin "1") (pinfunction "1_1") (pintype "passive"))
      (node (ref "R10") (pin "1") (pinfunction "1_1") (pintype "passive"))
    )
    (net (code "29") (name "Net-(A8-Pad1)") (class "Default")
      (node (ref "A8") (pin "1") (pinfunction "1_1") (pintype "passive"))
      (node (ref "R14") (pin "1") (pinfunction "1_1") (pintype "passive"))
    )
    (net (code "30") (name "Net-(A9-Pad1)") (class "Default")
      (node (ref "A9") (pin "1") (pinfunction "1_1") (pintype "passive"))
      (node (ref "R3") (pin "1") (pinfunction "1_1") (pintype "passive"))
    )
    (net (code "31") (name "Net-(A10-Pad1)") (class "Default")
      (node (ref "A10") (pin "1") (pinfunction "1_1") (pintype "passive"))
      (node (ref "R7") (pin "1") (pinfunction "1_1") (pintype "passive"))
    )
    (net (code "32") (name "Net-(A11-Pad1)") (class "Default")
      (node (ref "A11") (pin "1") (pinfunction "1_1") (pintype "passive"))
      (node (ref "R11") (pin "1") (pinfunction "1_1") (pintype "passive"))
    )
    (net (code "33") (name "Net-(A12-Pad1)") (class "Default")
      (node (ref "A12") (pin "1") (pinfunction "1_1") (pintype "passive"))
      (node (ref "R15") (pin "1") (pinfunction "1_1") (pintype "passive"))
    )
    (net (code "34") (name "Net-(A13-Pad1)") (class "Default")
      (node (ref "A13") (pin "1") (pinfunction "1_1") (pintype "passive"))
      (node (ref "R4") (pin "1") (pinfunction "1_1") (pintype "passive"))
    )
    (net (code "35") (name "Net-(A14-Pad1)") (class "Default")
      (node (ref "A14") (pin "1") (pinfunction "1_1") (pintype "passive"))
      (node (ref "R8") (pin "1") (pinfunction "1_1") (pintype "passive"))
    )
    (net (code "36") (name "Net-(A15-Pad1)") (class "Default")
      (node (ref "A15") (pin "1") (pinfunction "1_1") (pintype "passive"))
      (node (ref "R12") (pin "1") (pinfunction "1_1") (pintype "passive"))
    )
    (net (code "37") (name "Net-(A16-Pad1)") (class "Default")
      (node (ref "A16") (pin "1") (pinfunction "1_1") (pintype "passive"))
      (node (ref "R16") (pin "1") (pinfunction "1_1") (pintype "passive"))
    )
    (net (code "38") (name "Net-(A17-Pad1)") (class "Default")
      (node (ref "A17") (pin "1") (pinfunction "1_1") (pintype "passive"))
      (node (ref "R17") (pin "1") (pinfunction "1_1") (pintype "passive"))
    )
    (net (code "39") (name "Net-(A18-Pad1)") (class "Default")
      (node (ref "A18") (pin "1") (pinfunction "1_1") (pintype "passive"))
      (node (ref "R21") (pin "1") (pinfunction "1_1") (pintype "passive"))
    )
    (net (code "40") (name "Net-(A19-Pad1)") (class "Default")
      (node (ref "A19") (pin "1") (pinfunction "1_1") (pintype "passive"))
      (node (ref "R25") (pin "1") (pinfunction "1_1") (pintype "passive"))
    )
    (net (code "41") (name "Net-(A20-Pad1)") (class "Default")
      (node (ref "A20") (pin "1") (pinfunction "1_1") (pintype "passive"))
      (node (ref "R29") (pin "1") (pinfunction "1_1") (pintype "passive"))
    )
    (net (code "42") (name "Net-(A21-Pad1)") (class "Default")
      (node (ref "A21") (pin "1") (pinfunction "1_1") (pintype "passive"))
      (node (ref "R18") (pin "1") (pinfunction "1_1") (pintype "passive"))
    )
    (net (code "43") (name "Net-(A22-Pad1)") (class "Default")
      (node (ref "A22") (pin "1") (pinfunction "1_1") (pintype "passive"))
      (node (ref "R22") (pin "1") (pinfunction "1_1") (pintype "passive"))
    )
    (net (code "44") (name "Net-(A23-Pad1)") (class "Default")
      (node (ref "A23") (pin "1") (pinfunction "1_1") (pintype "passive"))
      (node (ref "R26") (pin "1") (pinfunction "1_1") (pintype "passive"))
    )
    (net (code "45") (name "Net-(A24-Pad1)") (class "Default")
      (node (ref "A24") (pin "1") (pinfunction "1_1") (pintype "passive"))
      (node (ref "R30") (pin "1") (pinfunction "1_1") (pintype "passive"))
    )
    (net (code "46") (name "Net-(A25-Pad1)") (class "Default")
      (node (ref "A25") (pin "1") (pinfunction "1_1") (pintype "passive"))
      (node (ref "R19") (pin "1") (pinfunction "1_1") (pintype "passive"))
    )
    (net (code "47") (name "Net-(A26-Pad1)") (class "Default")
      (node (ref "A26") (pin "1") (pinfunction "1_1") (pintype "passive"))
      (node (ref "R23") (pin "1") (pinfunction "1_1") (pintype "passive"))
    )
    (net (code "48") (name "Net-(A27-Pad1)") (class "Default")
      (node (ref "A27") (pin "1") (pinfunction "1_1") (pintype "passive"))
      (node (ref "R27") (pin "1") (pinfunction "1_1") (pintype "passive"))
    )
    (net (code "49") (name "Net-(A28-Pad1)") (class "Default")
      (node (ref "A28") (pin "1") (pinfunction "1_1") (pintype "passive"))
      (node (ref "R31") (pin "1") (pinfunction "1_1") (pintype "passive"))
    )
    (net (code "50") (name "Net-(A29-Pad1)") (class "Default")
      (node (ref "A29") (pin "1") (pinfunction "1_1") (pintype "passive"))
      (node (ref "R20") (pin "1") (pinfunction "1_1") (pintype "passive"))
    )
    (net (code "51") (name "Net-(A30-Pad1)") (class "Default")
      (node (ref "A30") (pin "1") (pinfunction "1_1") (pintype "passive"))
      (node (ref "R24") (pin "1") (pinfunction "1_1") (pintype "passive"))
    )
    (net (code "52") (name "Net-(A31-Pad1)") (class "Default")
      (node (ref "A31") (pin "1") (pinfunction "1_1") (pintype "passive"))
      (node (ref "R28") (pin "1") (pinfunction "1_1") (pintype "passive"))
    )
    (net (code "53") (name "Net-(A32-Pad1)") (class "Default")
      (node (ref "A32") (pin "1") (pinfunction "1_1") (pintype "passive"))
      (node (ref "R32") (pin "1") (pinfunction "1_1") (pintype "passive"))
    )
    (net (code "54") (name "Net-(A33-Pad1)") (class "Default")
      (node (ref "A33") (pin "1") (pinfunction "1_1") (pintype "passive"))
      (node (ref "R33") (pin "1") (pinfunction "1_1") (pintype "passive"))
    )
    (net (code "55") (name "Net-(A34-Pad1)") (class "Default")
      (node (ref "A34") (pin "1") (pinfunction "1_1") (pintype "passive"))
      (node (ref "R37") (pin "1") (pinfunction "1_1") (pintype "passive"))
    )
    (net (code "56") (name "Net-(A35-Pad1)") (class "Default")
      (node (ref "A35") (pin "1") (pinfunction "1_1") (pintype "passive"))
      (node (ref "R41") (pin "1") (pinfunction "1_1") (pintype "passive"))
    )
    (net (code "57") (name "Net-(A36-Pad1)") (class "Default")
      (node (ref "A36") (pin "1") (pinfunction "1_1") (pintype "passive"))
      (node (ref "R45") (pin "1") (pinfunction "1_1") (pintype "passive"))
    )
    (net (code "58") (name "Net-(A37-Pad1)") (class "Default")
      (node (ref "A37") (pin "1") (pinfunction "1_1") (pintype "passive"))
      (node (ref "R34") (pin "1") (pinfunction "1_1") (pintype "passive"))
    )
    (net (code "59") (name "Net-(A38-Pad1)") (class "Default")
      (node (ref "A38") (pin "1") (pinfunction "1_1") (pintype "passive"))
      (node (ref "R38") (pin "1") (pinfunction "1_1") (pintype "passive"))
    )
    (net (code "60") (name "Net-(A39-Pad1)") (class "Default")
      (node (ref "A39") (pin "1") (pinfunction "1_1") (pintype "passive"))
      (node (ref "R42") (pin "1") (pinfunction "1_1") (pintype "passive"))
    )
    (net (code "61") (name "Net-(A40-Pad1)") (class "Default")
      (node (ref "A40") (pin "1") (pinfunction "1_1") (pintype "passive"))
      (node (ref "R46") (pin "1") (pinfunction "1_1") (pintype "passive"))
    )
    (net (code "62") (name "Net-(A41-Pad1)") (class "Default")
      (node (ref "A41") (pin "1") (pinfunction "1_1") (pintype "passive"))
      (node (ref "R35") (pin "1") (pinfunction "1_1") (pintype "passive"))
    )
    (net (code "63") (name "Net-(A42-Pad1)") (class "Default")
      (node (ref "A42") (pin "1") (pinfunction "1_1") (pintype "passive"))
      (node (ref "R39") (pin "1") (pinfunction "1_1") (pintype "passive"))
    )
    (net (code "64") (name "Net-(A43-Pad1)") (class "Default")
      (node (ref "A43") (pin "1") (pinfunction "1_1") (pintype "passive"))
      (node (ref "R43") (pin "1") (pinfunction "1_1") (pintype "passive"))
    )
    (net (code "65") (name "Net-(A44-Pad1)") (class "Default")
      (node (ref "A44") (pin "1") (pinfunction "1_1") (pintype "passive"))
      (node (ref "R47") (pin "1") (pinfunction "1_1") (pintype "passive"))
    )
    (net (code "66") (name "Net-(A45-Pad1)") (class "Default")
      (node (ref "A45") (pin "1") (pinfunction "1_1") (pintype "passive"))
      (node (ref "R36") (pin "1") (pinfunction "1_1") (pintype "passive"))
    )
    (net (code "67") (name "Net-(A46-Pad1)") (class "Default")
      (node (ref "A46") (pin "1") (pinfunction "1_1") (pintype "passive"))
      (node (ref "R40") (pin "1") (pinfunction "1_1") (pintype "passive"))
    )
    (net (code "68") (name "Net-(A47-Pad1)") (class "Default")
      (node (ref "A47") (pin "1") (pinfunction "1_1") (pintype "passive"))
      (node (ref "R44") (pin "1") (pinfunction "1_1") (pintype "passive"))
    )
    (net (code "69") (name "Net-(A48-Pad1)") (class "Default")
      (node (ref "A48") (pin "1") (pinfunction "1_1") (pintype "passive"))
      (node (ref "R48") (pin "1") (pinfunction "1_1") (pintype "passive"))
    )
    (net (code "70") (name "Net-(A49-Pad1)") (class "Default")
      (node (ref "A49") (pin "1") (pinfunction "1_1") (pintype "passive"))
      (node (ref "R49") (pin "1") (pinfunction "1_1") (pintype "passive"))
    )
    (net (code "71") (name "Net-(A50-Pad1)") (class "Default")
      (node (ref "A50") (pin "1") (pinfunction "1_1") (pintype "passive"))
      (node (ref "R53") (pin "1") (pinfunction "1_1") (pintype "passive"))
    )
    (net (code "72") (name "Net-(A51-Pad1)") (class "Default")
      (node (ref "A51") (pin "1") (pinfunction "1_1") (pintype "passive"))
      (node (ref "R57") (pin "1") (pinfunction "1_1") (pintype "passive"))
    )
    (net (code "73") (name "Net-(A52-Pad1)") (class "Default")
      (node (ref "A52") (pin "1") (pinfunction "1_1") (pintype "passive"))
      (node (ref "R61") (pin "1") (pinfunction "1_1") (pintype "passive"))
    )
    (net (code "74") (name "Net-(A53-Pad1)") (class "Default")
      (node (ref "A53") (pin "1") (pinfunction "1_1") (pintype "passive"))
      (node (ref "R50") (pin "1") (pinfunction "1_1") (pintype "passive"))
    )
    (net (code "75") (name "Net-(A54-Pad1)") (class "Default")
      (node (ref "A54") (pin "1") (pinfunction "1_1") (pintype "passive"))
      (node (ref "R54") (pin "1") (pinfunction "1_1") (pintype "passive"))
    )
    (net (code "76") (name "Net-(A55-Pad1)") (class "Default")
      (node (ref "A55") (pin "1") (pinfunction "1_1") (pintype "passive"))
      (node (ref "R58") (pin "1") (pinfunction "1_1") (pintype "passive"))
    )
    (net (code "77") (name "Net-(A56-Pad1)") (class "Default")
      (node (ref "A56") (pin "1") (pinfunction "1_1") (pintype "passive"))
      (node (ref "R62") (pin "1") (pinfunction "1_1") (pintype "passive"))
    )
    (net (code "78") (name "Net-(A57-Pad1)") (class "Default")
      (node (ref "A57") (pin "1") (pinfunction "1_1") (pintype "passive"))
      (node (ref "R51") (pin "1") (pinfunction "1_1") (pintype "passive"))
    )
    (net (code "79") (name "Net-(A58-Pad1)") (class "Default")
      (node (ref "A58") (pin "1") (pinfunction "1_1") (pintype "passive"))
      (node (ref "R55") (pin "1") (pinfunction "1_1") (pintype "passive"))
    )
    (net (code "80") (name "Net-(A59-Pad1)") (class "Default")
      (node (ref "A59") (pin "1") (pinfunction "1_1") (pintype "passive"))
      (node (ref "R59") (pin "1") (pinfunction "1_1") (pintype "passive"))
    )
    (net (code "81") (name "Net-(A60-Pad1)") (class "Default")
      (node (ref "A60") (pin "1") (pinfunction "1_1") (pintype "passive"))
      (node (ref "R63") (pin "1") (pinfunction "1_1") (pintype "passive"))
    )
    (net (code "82") (name "Net-(A61-Pad1)") (class "Default")
      (node (ref "A61") (pin "1") (pinfunction "1_1") (pintype "passive"))
      (node (ref "R52") (pin "1") (pinfunction "1_1") (pintype "passive"))
    )
    (net (code "83") (name "Net-(A62-Pad1)") (class "Default")
      (node (ref "A62") (pin "1") (pinfunction "1_1") (pintype "passive"))
      (node (ref "R56") (pin "1") (pinfunction "1_1") (pintype "passive"))
    )
    (net (code "84") (name "Net-(A63-Pad1)") (class "Default")
      (node (ref "A63") (pin "1") (pinfunction "1_1") (pintype "passive"))
      (node (ref "R60") (pin "1") (pinfunction "1_1") (pintype "passive"))
    )
    (net (code "85") (name "Net-(A64-Pad1)") (class "Default")
      (node (ref "A64") (pin "1") (pinfunction "1_1") (pintype "passive"))
      (node (ref "R64") (pin "1") (pinfunction "1_1") (pintype "passive"))
    )
    (net (code "86") (name "Net-(CAT1-Pad1)") (class "Default")
      (node (ref "CAT1") (pin "1") (pinfunction "1_1") (pintype "passive"))
      (node (ref "T2") (pin "D") (pinfunction "D_D") (pintype "passive"))
    )
    (net (code "87") (name "Net-(CAT2-Pad1)") (class "Default")
      (node (ref "CAT2") (pin "1") (pinfunction "1_1") (pintype "passive"))
      (node (ref "T1") (pin "D") (pinfunction "D_D") (pintype "passive"))
    )
    (net (code "88") (name "Net-(CAT3-Pad1)") (class "Default")
      (node (ref "CAT3") (pin "1") (pinfunction "1_1") (pintype "passive"))
      (node (ref "T3") (pin "D") (pinfunction "D_D") (pintype "passive"))
    )
    (net (code "89") (name "Net-(CAT4-Pad1)") (class "Default")
      (node (ref "CAT4") (pin "1") (pinfunction "1_1") (pintype "passive"))
      (node (ref "T4") (pin "D") (pinfunction "D_D") (pintype "passive"))
    )
    (net (code "90") (name "Net-(CAT5-Pad1)") (class "Default")
      (node (ref "CAT5") (pin "1") (pinfunction "1_1") (pintype "passive"))
      (node (ref "T8") (pin "D") (pinfunction "D_D") (pintype "passive"))
    )
    (net (code "91") (name "Net-(CAT6-Pad1)") (class "Default")
      (node (ref "CAT6") (pin "1") (pinfunction "1_1") (pintype "passive"))
      (node (ref "T7") (pin "D") (pinfunction "D_D") (pintype "passive"))
    )
    (net (code "92") (name "Net-(CAT7-Pad1)") (class "Default")
      (node (ref "CAT7") (pin "1") (pinfunction "1_1") (pintype "passive"))
      (node (ref "T6") (pin "D") (pinfunction "D_D") (pintype "passive"))
    )
    (net (code "93") (name "Net-(CAT8-Pad1)") (class "Default")
      (node (ref "CAT8") (pin "1") (pinfunction "1_1") (pintype "passive"))
      (node (ref "T5") (pin "D") (pinfunction "D_D") (pintype "passive"))
    )
    (net (code "94") (name "Net-(R65-Pad1)") (class "Default")
      (node (ref "R65") (pin "1") (pinfunction "1_1") (pintype "passive"))
      (node (ref "R83") (pin "2") (pinfunction "2_2") (pintype "passive"))
      (node (ref "T8") (pin "G") (pinfunction "G_G") (pintype "passive"))
    )
    (net (code "95") (name "Net-(R66-Pad1)") (class "Default")
      (node (ref "R66") (pin "1") (pinfunction "1_1") (pintype "passive"))
      (node (ref "R76") (pin "1") (pinfunction "1_1") (pintype "passive"))
      (node (ref "T2") (pin "G") (pinfunction "G_G") (pintype "passive"))
    )
    (net (code "96") (name "Net-(R67-Pad1)") (class "Default")
      (node (ref "R67") (pin "1") (pinfunction "1_1") (pintype "passive"))
      (node (ref "R82") (pin "1") (pinfunction "1_1") (pintype "passive"))
      (node (ref "T7") (pin "G") (pinfunction "G_G") (pintype "passive"))
    )
    (net (code "97") (name "Net-(R68-Pad1)") (class "Default")
      (node (ref "R68") (pin "1") (pinfunction "1_1") (pintype "passive"))
      (node (ref "R77") (pin "1") (pinfunction "1_1") (pintype "passive"))
      (node (ref "T1") (pin "G") (pinfunction "G_G") (pintype "passive"))
    )
    (net (code "98") (name "Net-(R69-Pad1)") (class "Default")
      (node (ref "R69") (pin "1") (pinfunction "1_1") (pintype "passive"))
      (node (ref "R81") (pin "1") (pinfunction "1_1") (pintype "passive"))
      (node (ref "T6") (pin "G") (pinfunction "G_G") (pintype "passive"))
    )
    (net (code "99") (name "Net-(R70-Pad1)") (class "Default")
      (node (ref "R70") (pin "1") (pinfunction "1_1") (pintype "passive"))
      (node (ref "R78") (pin "1") (pinfunction "1_1") (pintype "passive"))
      (node (ref "T3") (pin "G") (pinfunction "G_G") (pintype "passive"))
    )
    (net (code "100") (name "Net-(R71-Pad1)") (class "Default")
      (node (ref "R71") (pin "1") (pinfunction "1_1") (pintype "passive"))
      (node (ref "R80") (pin "1") (pinfunction "1_1") (pintype "passive"))
      (node (ref "T5") (pin "G") (pinfunction "G_G") (pintype "passive"))
    )
    (net (code "101") (name "Net-(R72-Pad1)") (class "Default")
      (node (ref "R72") (pin "1") (pinfunction "1_1") (pintype "passive"))
      (node (ref "R79") (pin "1") (pinfunction "1_1") (pintype "passive"))
      (node (ref "T4") (pin "G") (pinfunction "G_G") (pintype "passive"))
    )
    (net (code "102") (name "Net-(U1-Q0)") (class "Default")
      (node (ref "R1") (pin "2") (pinfunction "2_2") (pintype "passive"))
      (node (ref "U1") (pin "4") (pinfunction "Q0_4") (pintype "passive"))
    )
    (net (code "103") (name "Net-(U1-Q1)") (class "Default")
      (node (ref "R5") (pin "2") (pinfunction "2_2") (pintype "passive"))
      (node (ref "U1") (pin "5") (pinfunction "Q1_5") (pintype "passive"))
    )
    (net (code "104") (name "Net-(U1-Q2)") (class "Default")
      (node (ref "R9") (pin "2") (pinfunction "2_2") (pintype "passive"))
      (node (ref "U1") (pin "6") (pinfunction "Q2_6") (pintype "passive"))
    )
    (net (code "105") (name "Net-(U1-Q3)") (class "Default")
      (node (ref "R13") (pin "2") (pinfunction "2_2") (pintype "passive"))
      (node (ref "U1") (pin "7") (pinfunction "Q3_7") (pintype "passive"))
    )
    (net (code "106") (name "Net-(U2-Q0)") (class "Default")
      (node (ref "R2") (pin "2") (pinfunction "2_2") (pintype "passive"))
      (node (ref "U2") (pin "4") (pinfunction "Q0_4") (pintype "passive"))
    )
    (net (code "107") (name "Net-(U2-Q1)") (class "Default")
      (node (ref "R6") (pin "2") (pinfunction "2_2") (pintype "passive"))
      (node (ref "U2") (pin "5") (pinfunction "Q1_5") (pintype "passive"))
    )
    (net (code "108") (name "Net-(U2-Q2)") (class "Default")
      (node (ref "R10") (pin "2") (pinfunction "2_2") (pintype "passive"))
      (node (ref "U2") (pin "6") (pinfunction "Q2_6") (pintype "passive"))
    )
    (net (code "109") (name "Net-(U2-Q3)") (class "Default")
      (node (ref "R14") (pin "2") (pinfunction "2_2") (pintype "passive"))
      (node (ref "U2") (pin "7") (pinfunction "Q3_7") (pintype "passive"))
    )
    (net (code "110") (name "Net-(U3-Q0)") (class "Default")
      (node (ref "R3") (pin "2") (pinfunction "2_2") (pintype "passive"))
      (node (ref "U3") (pin "4") (pinfunction "Q0_4") (pintype "passive"))
    )
    (net (code "111") (name "Net-(U3-Q1)") (class "Default")
      (node (ref "R7") (pin "2") (pinfunction "2_2") (pintype "passive"))
      (node (ref "U3") (pin "5") (pinfunction "Q1_5") (pintype "passive"))
    )
    (net (code "112") (name "Net-(U3-Q2)") (class "Default")
      (node (ref "R11") (pin "2") (pinfunction "2_2") (pintype "passive"))
      (node (ref "U3") (pin "6") (pinfunction "Q2_6") (pintype "passive"))
    )
    (net (code "113") (name "Net-(U3-Q3)") (class "Default")
      (node (ref "R15") (pin "2") (pinfunction "2_2") (pintype "passive"))
      (node (ref "U3") (pin "7") (pinfunction "Q3_7") (pintype "passive"))
    )
    (net (code "114") (name "Net-(U4-Q0)") (class "Default")
      (node (ref "R4") (pin "2") (pinfunction "2_2") (pintype "passive"))
      (node (ref "U4") (pin "4") (pinfunction "Q0_4") (pintype "passive"))
    )
    (net (code "115") (name "Net-(U4-Q1)") (class "Default")
      (node (ref "R8") (pin "2") (pinfunction "2_2") (pintype "passive"))
      (node (ref "U4") (pin "5") (pinfunction "Q1_5") (pintype "passive"))
    )
    (net (code "116") (name "Net-(U4-Q2)") (class "Default")
      (node (ref "R12") (pin "2") (pinfunction "2_2") (pintype "passive"))
      (node (ref "U4") (pin "6") (pinfunction "Q2_6") (pintype "passive"))
    )
    (net (code "117") (name "Net-(U4-Q3)") (class "Default")
      (node (ref "R16") (pin "2") (pinfunction "2_2") (pintype "passive"))
      (node (ref "U4") (pin "7") (pinfunction "Q3_7") (pintype "passive"))
    )
    (net (code "118") (name "Net-(U5-Q0)") (class "Default")
      (node (ref "R17") (pin "2") (pinfunction "2_2") (pintype "passive"))
      (node (ref "U5") (pin "4") (pinfunction "Q0_4") (pintype "passive"))
    )
    (net (code "119") (name "Net-(U5-Q1)") (class "Default")
      (node (ref "R21") (pin "2") (pinfunction "2_2") (pintype "passive"))
      (node (ref "U5") (pin "5") (pinfunction "Q1_5") (pintype "passive"))
    )
    (net (code "120") (name "Net-(U5-Q2)") (class "Default")
      (node (ref "R25") (pin "2") (pinfunction "2_2") (pintype "passive"))
      (node (ref "U5") (pin "6") (pinfunction "Q2_6") (pintype "passive"))
    )
    (net (code "121") (name "Net-(U5-Q3)") (class "Default")
      (node (ref "R29") (pin "2") (pinfunction "2_2") (pintype "passive"))
      (node (ref "U5") (pin "7") (pinfunction "Q3_7") (pintype "passive"))
    )
    (net (code "122") (name "Net-(U6-Q0)") (class "Default")
      (node (ref "R18") (pin "2") (pinfunction "2_2") (pintype "passive"))
      (node (ref "U6") (pin "4") (pinfunction "Q0_4") (pintype "passive"))
    )
    (net (code "123") (name "Net-(U6-Q1)") (class "Default")
      (node (ref "R22") (pin "2") (pinfunction "2_2") (pintype "passive"))
      (node (ref "U6") (pin "5") (pinfunction "Q1_5") (pintype "passive"))
    )
    (net (code "124") (name "Net-(U6-Q2)") (class "Default")
      (node (ref "R26") (pin "2") (pinfunction "2_2") (pintype "passive"))
      (node (ref "U6") (pin "6") (pinfunction "Q2_6") (pintype "passive"))
    )
    (net (code "125") (name "Net-(U6-Q3)") (class "Default")
      (node (ref "R30") (pin "2") (pinfunction "2_2") (pintype "passive"))
      (node (ref "U6") (pin "7") (pinfunction "Q3_7") (pintype "passive"))
    )
    (net (code "126") (name "Net-(U7-Q0)") (class "Default")
      (node (ref "R19") (pin "2") (pinfunction "2_2") (pintype "passive"))
      (node (ref "U7") (pin "4") (pinfunction "Q0_4") (pintype "passive"))
    )
    (net (code "127") (name "Net-(U7-Q1)") (class "Default")
      (node (ref "R23") (pin "2") (pinfunction "2_2") (pintype "passive"))
      (node (ref "U7") (pin "5") (pinfunction "Q1_5") (pintype "passive"))
    )
    (net (code "128") (name "Net-(U7-Q2)") (class "Default")
      (node (ref "R27") (pin "2") (pinfunction "2_2") (pintype "passive"))
      (node (ref "U7") (pin "6") (pinfunction "Q2_6") (pintype "passive"))
    )
    (net (code "129") (name "Net-(U7-Q3)") (class "Default")
      (node (ref "R31") (pin "2") (pinfunction "2_2") (pintype "passive"))
      (node (ref "U7") (pin "7") (pinfunction "Q3_7") (pintype "passive"))
    )
    (net (code "130") (name "Net-(U8-Q0)") (class "Default")
      (node (ref "R20") (pin "2") (pinfunction "2_2") (pintype "passive"))
      (node (ref "U8") (pin "4") (pinfunction "Q0_4") (pintype "passive"))
    )
    (net (code "131") (name "Net-(U8-Q1)") (class "Default")
      (node (ref "R24") (pin "2") (pinfunction "2_2") (pintype "passive"))
      (node (ref "U8") (pin "5") (pinfunction "Q1_5") (pintype "passive"))
    )
    (net (code "132") (name "Net-(U8-Q2)") (class "Default")
      (node (ref "R28") (pin "2") (pinfunction "2_2") (pintype "passive"))
      (node (ref "U8") (pin "6") (pinfunction "Q2_6") (pintype "passive"))
    )
    (net (code "133") (name "Net-(U8-Q3)") (class "Default")
      (node (ref "R32") (pin "2") (pinfunction "2_2") (pintype "passive"))
      (node (ref "U8") (pin "7") (pinfunction "Q3_7") (pintype "passive"))
    )
    (net (code "134") (name "Net-(U9-Q0)") (class "Default")
      (node (ref "R33") (pin "2") (pinfunction "2_2") (pintype "passive"))
      (node (ref "U9") (pin "4") (pinfunction "Q0_4") (pintype "passive"))
    )
    (net (code "135") (name "Net-(U9-Q1)") (class "Default")
      (node (ref "R37") (pin "2") (pinfunction "2_2") (pintype "passive"))
      (node (ref "U9") (pin "5") (pinfunction "Q1_5") (pintype "passive"))
    )
    (net (code "136") (name "Net-(U9-Q2)") (class "Default")
      (node (ref "R41") (pin "2") (pinfunction "2_2") (pintype "passive"))
      (node (ref "U9") (pin "6") (pinfunction "Q2_6") (pintype "passive"))
    )
    (net (code "137") (name "Net-(U9-Q3)") (class "Default")
      (node (ref "R45") (pin "2") (pinfunction "2_2") (pintype "passive"))
      (node (ref "U9") (pin "7") (pinfunction "Q3_7") (pintype "passive"))
    )
    (net (code "138") (name "Net-(U10-Q0)") (class "Default")
      (node (ref "R34") (pin "2") (pinfunction "2_2") (pintype "passive"))
      (node (ref "U10") (pin "4") (pinfunction "Q0_4") (pintype "passive"))
    )
    (net (code "139") (name "Net-(U10-Q1)") (class "Default")
      (node (ref "R38") (pin "2") (pinfunction "2_2") (pintype "passive"))
      (node (ref "U10") (pin "5") (pinfunction "Q1_5") (pintype "passive"))
    )
    (net (code "140") (name "Net-(U10-Q2)") (class "Default")
      (node (ref "R42") (pin "2") (pinfunction "2_2") (pintype "passive"))
      (node (ref "U10") (pin "6") (pinfunction "Q2_6") (pintype "passive"))
    )
    (net (code "141") (name "Net-(U10-Q3)") (class "Default")
      (node (ref "R46") (pin "2") (pinfunction "2_2") (pintype "passive"))
      (node (ref "U10") (pin "7") (pinfunction "Q3_7") (pintype "passive"))
    )
    (net (code "142") (name "Net-(U11-Q0)") (class "Default")
      (node (ref "R35") (pin "2") (pinfunction "2_2") (pintype "passive"))
      (node (ref "U11") (pin "4") (pinfunction "Q0_4") (pintype "passive"))
    )
    (net (code "143") (name "Net-(U11-Q1)") (class "Default")
      (node (ref "R39") (pin "2") (pinfunction "2_2") (pintype "passive"))
      (node (ref "U11") (pin "5") (pinfunction "Q1_5") (pintype "passive"))
    )
    (net (code "144") (name "Net-(U11-Q2)") (class "Default")
      (node (ref "R43") (pin "2") (pinfunction "2_2") (pintype "passive"))
      (node (ref "U11") (pin "6") (pinfunction "Q2_6") (pintype "passive"))
    )
    (net (code "145") (name "Net-(U11-Q3)") (class "Default")
      (node (ref "R47") (pin "2") (pinfunction "2_2") (pintype "passive"))
      (node (ref "U11") (pin "7") (pinfunction "Q3_7") (pintype "passive"))
    )
    (net (code "146") (name "Net-(U12-Q0)") (class "Default")
      (node (ref "R36") (pin "2") (pinfunction "2_2") (pintype "passive"))
      (node (ref "U12") (pin "4") (pinfunction "Q0_4") (pintype "passive"))
    )
    (net (code "147") (name "Net-(U12-Q1)") (class "Default")
      (node (ref "R40") (pin "2") (pinfunction "2_2") (pintype "passive"))
      (node (ref "U12") (pin "5") (pinfunction "Q1_5") (pintype "passive"))
    )
    (net (code "148") (name "Net-(U12-Q2)") (class "Default")
      (node (ref "R44") (pin "2") (pinfunction "2_2") (pintype "passive"))
      (node (ref "U12") (pin "6") (pinfunction "Q2_6") (pintype "passive"))
    )
    (net (code "149") (name "Net-(U12-Q3)") (class "Default")
      (node (ref "R48") (pin "2") (pinfunction "2_2") (pintype "passive"))
      (node (ref "U12") (pin "7") (pinfunction "Q3_7") (pintype "passive"))
    )
    (net (code "150") (name "Net-(U13-Q0)") (class "Default")
      (node (ref "R49") (pin "2") (pinfunction "2_2") (pintype "passive"))
      (node (ref "U13") (pin "4") (pinfunction "Q0_4") (pintype "passive"))
    )
    (net (code "151") (name "Net-(U13-Q1)") (class "Default")
      (node (ref "R53") (pin "2") (pinfunction "2_2") (pintype "passive"))
      (node (ref "U13") (pin "5") (pinfunction "Q1_5") (pintype "passive"))
    )
    (net (code "152") (name "Net-(U13-Q2)") (class "Default")
      (node (ref "R57") (pin "2") (pinfunction "2_2") (pintype "passive"))
      (node (ref "U13") (pin "6") (pinfunction "Q2_6") (pintype "passive"))
    )
    (net (code "153") (name "Net-(U13-Q3)") (class "Default")
      (node (ref "R61") (pin "2") (pinfunction "2_2") (pintype "passive"))
      (node (ref "U13") (pin "7") (pinfunction "Q3_7") (pintype "passive"))
    )
    (net (code "154") (name "Net-(U14-Q0)") (class "Default")
      (node (ref "R50") (pin "2") (pinfunction "2_2") (pintype "passive"))
      (node (ref "U14") (pin "4") (pinfunction "Q0_4") (pintype "passive"))
    )
    (net (code "155") (name "Net-(U14-Q1)") (class "Default")
      (node (ref "R54") (pin "2") (pinfunction "2_2") (pintype "passive"))
      (node (ref "U14") (pin "5") (pinfunction "Q1_5") (pintype "passive"))
    )
    (net (code "156") (name "Net-(U14-Q2)") (class "Default")
      (node (ref "R58") (pin "2") (pinfunction "2_2") (pintype "passive"))
      (node (ref "U14") (pin "6") (pinfunction "Q2_6") (pintype "passive"))
    )
    (net (code "157") (name "Net-(U14-Q3)") (class "Default")
      (node (ref "R62") (pin "2") (pinfunction "2_2") (pintype "passive"))
      (node (ref "U14") (pin "7") (pinfunction "Q3_7") (pintype "passive"))
    )
    (net (code "158") (name "Net-(U15-Q0)") (class "Default")
      (node (ref "R51") (pin "2") (pinfunction "2_2") (pintype "passive"))
      (node (ref "U15") (pin "4") (pinfunction "Q0_4") (pintype "passive"))
    )
    (net (code "159") (name "Net-(U15-Q1)") (class "Default")
      (node (ref "R55") (pin "2") (pinfunction "2_2") (pintype "passive"))
      (node (ref "U15") (pin "5") (pinfunction "Q1_5") (pintype "passive"))
    )
    (net (code "160") (name "Net-(U15-Q2)") (class "Default")
      (node (ref "R59") (pin "2") (pinfunction "2_2") (pintype "passive"))
      (node (ref "U15") (pin "6") (pinfunction "Q2_6") (pintype "passive"))
    )
    (net (code "161") (name "Net-(U15-Q3)") (class "Default")
      (node (ref "R63") (pin "2") (pinfunction "2_2") (pintype "passive"))
      (node (ref "U15") (pin "7") (pinfunction "Q3_7") (pintype "passive"))
    )
    (net (code "162") (name "Net-(U16-Q0)") (class "Default")
      (node (ref "R52") (pin "2") (pinfunction "2_2") (pintype "passive"))
      (node (ref "U16") (pin "4") (pinfunction "Q0_4") (pintype "passive"))
    )
    (net (code "163") (name "Net-(U16-Q1)") (class "Default")
      (node (ref "R56") (pin "2") (pinfunction "2_2") (pintype "passive"))
      (node (ref "U16") (pin "5") (pinfunction "Q1_5") (pintype "passive"))
    )
    (net (code "164") (name "Net-(U16-Q2)") (class "Default")
      (node (ref "R60") (pin "2") (pinfunction "2_2") (pintype "passive"))
      (node (ref "U16") (pin "6") (pinfunction "Q2_6") (pintype "passive"))
    )
    (net (code "165") (name "Net-(U16-Q3)") (class "Default")
      (node (ref "R64") (pin "2") (pinfunction "2_2") (pintype "passive"))
      (node (ref "U16") (pin "7") (pinfunction "Q3_7") (pintype "passive"))
    )
    (net (code "166") (name "Net-(U17-Q0)") (class "Default")
      (node (ref "R66") (pin "2") (pinfunction "2_2") (pintype "passive"))
      (node (ref "U17") (pin "4") (pinfunction "Q0_4") (pintype "passive"))
    )
    (net (code "167") (name "Net-(U17-Q1)") (class "Default")
      (node (ref "R68") (pin "2") (pinfunction "2_2") (pintype "passive"))
      (node (ref "U17") (pin "5") (pinfunction "Q1_5") (pintype "passive"))
    )
    (net (code "168") (name "Net-(U17-Q2)") (class "Default")
      (node (ref "R70") (pin "2") (pinfunction "2_2") (pintype "passive"))
      (node (ref "U17") (pin "6") (pinfunction "Q2_6") (pintype "passive"))
    )
    (net (code "169") (name "Net-(U17-Q3)") (class "Default")
      (node (ref "R72") (pin "2") (pinfunction "2_2") (pintype "passive"))
      (node (ref "U17") (pin "7") (pinfunction "Q3_7") (pintype "passive"))
    )
    (net (code "170") (name "Net-(U17-Q4)") (class "Default")
      (node (ref "R65") (pin "2") (pinfunction "2_2") (pintype "passive"))
      (node (ref "U17") (pin "14") (pinfunction "Q4_14") (pintype "passive"))
    )
    (net (code "171") (name "Net-(U17-Q5)") (class "Default")
      (node (ref "R67") (pin "2") (pinfunction "2_2") (pintype "passive"))
      (node (ref "U17") (pin "13") (pinfunction "Q5_13") (pintype "passive"))
    )
    (net (code "172") (name "Net-(U17-Q6)") (class "Default")
      (node (ref "R69") (pin "2") (pinfunction "2_2") (pintype "passive"))
      (node (ref "U17") (pin "12") (pinfunction "Q6_12") (pintype "passive"))
    )
    (net (code "173") (name "Net-(U17-Q7)") (class "Default")
      (node (ref "R71") (pin "2") (pinfunction "2_2") (pintype "passive"))
      (node (ref "U17") (pin "11") (pinfunction "Q7_11") (pintype "passive"))
    )
    (net (code "174") (name "Net-(U18-COMP)") (class "Default")
      (node (ref "R74") (pin "1") (pinfunction "1_1") (pintype "passive"))
      (node (ref "R75") (pin "1") (pinfunction "1_1") (pintype "passive"))
      (node (ref "U18") (pin "5") (pinfunction "COMP_5") (pintype "input"))
    )
    (net (code "175") (name "Net-(U18-IDC)") (class "Default")
      (node (ref "R73") (pin "2") (pinfunction "2_2") (pintype "passive"))
      (node (ref "U18") (pin "1") (pinfunction "ISWC_1") (pintype "output"))
      (node (ref "U18") (pin "7") (pinfunction "IPK_7") (pintype "passive"))
      (node (ref "U18") (pin "8") (pinfunction "IDC_8") (pintype "passive"))
    )
    (net (code "176") (name "Net-(U18-ISWE)") (class "Default")
      (node (ref "D1") (pin "1") (pinfunction "1_1") (pintype "passive"))
      (node (ref "L1") (pin "1") (pinfunction "1_1") (pintype "passive"))
      (node (ref "U18") (pin "2") (pinfunction "ISWE_2") (pintype "output"))
    )
    (net (code "177") (name "Net-(U18-TCAP)") (class "Default")
      (node (ref "C2") (pin "2") (pinfunction "2_2") (pintype "passive"))
      (node (ref "U18") (pin "3") (pinfunction "TCAP_3") (pintype "passive"))
    )
    (net (code "178") (name "VCC") (class "Default")
      (node (ref "C3") (pin "P") (pinfunction "P_P") (pintype "passive"))
      (node (ref "L1") (pin "2") (pinfunction "2_2") (pintype "passive"))
      (node (ref "P1") (pin "1") (pinfunction "1_1") (pintype "passive"))
      (node (ref "R75") (pin "2") (pinfunction "2_2") (pintype "passive"))
      (node (ref "U1") (pin "15") (pinfunction "OE_15") (pintype "passive"))
      (node (ref "U1") (pin "16") (pinfunction "VCC_16") (pintype "passive"))
      (node (ref "U10") (pin "15") (pinfunction "OE_15") (pintype "passive"))
      (node (ref "U10") (pin "16") (pinfunction "VCC_16") (pintype "passive"))
      (node (ref "U11") (pin "15") (pinfunction "OE_15") (pintype "passive"))
      (node (ref "U11") (pin "16") (pinfunction "VCC_16") (pintype "passive"))
      (node (ref "U12") (pin "15") (pinfunction "OE_15") (pintype "passive"))
      (node (ref "U12") (pin "16") (pinfunction "VCC_16") (pintype "passive"))
      (node (ref "U13") (pin "15") (pinfunction "OE_15") (pintype "passive"))
      (node (ref "U13") (pin "16") (pinfunction "VCC_16") (pintype "passive"))
      (node (ref "U14") (pin "15") (pinfunction "OE_15") (pintype "passive"))
      (node (ref "U14") (pin "16") (pinfunction "VCC_16") (pintype "passive"))
      (node (ref "U15") (pin "15") (pinfunction "OE_15") (pintype "passive"))
      (node (ref "U15") (pin "16") (pinfunction "VCC_16") (pintype "passive"))
      (node (ref "U16") (pin "15") (pinfunction "OE_15") (pintype "passive"))
      (node (ref "U16") (pin "16") (pinfunction "VCC_16") (pintype "passive"))
      (node (ref "U17") (pin "16") (pinfunction "VCC_16") (pintype "passive"))
      (node (ref "U2") (pin "15") (pinfunction "OE_15") (pintype "passive"))
      (node (ref "U2") (pin "16") (pinfunction "VCC_16") (pintype "passive"))
      (node (ref "U3") (pin "15") (pinfunction "OE_15") (pintype "passive"))
      (node (ref "U3") (pin "16") (pinfunction "VCC_16") (pintype "passive"))
      (node (ref "U4") (pin "15") (pinfunction "OE_15") (pintype "passive"))
      (node (ref "U4") (pin "16") (pinfunction "VCC_16") (pintype "passive"))
      (node (ref "U5") (pin "15") (pinfunction "OE_15") (pintype "passive"))
      (node (ref "U5") (pin "16") (pinfunction "VCC_16") (pintype "passive"))
      (node (ref "U6") (pin "15") (pinfunction "OE_15") (pintype "passive"))
      (node (ref "U6") (pin "16") (pinfunction "VCC_16") (pintype "passive"))
      (node (ref "U7") (pin "15") (pinfunction "OE_15") (pintype "passive"))
      (node (ref "U7") (pin "16") (pinfunction "VCC_16") (pintype "passive"))
      (node (ref "U8") (pin "15") (pinfunction "OE_15") (pintype "passive"))
      (node (ref "U8") (pin "16") (pinfunction "VCC_16") (pintype "passive"))
      (node (ref "U9") (pin "15") (pinfunction "OE_15") (pintype "passive"))
      (node (ref "U9") (pin "16") (pinfunction "VCC_16") (pintype "passive"))
    )
    (net (code "179") (name "VIN") (class "Default")
      (node (ref "C1") (pin "P") (pinfunction "P_P") (pintype "passive"))
      (node (ref "P2") (pin "1") (pinfunction "1_1") (pintype "passive"))
      (node (ref "R73") (pin "1") (pinfunction "1_1") (pintype "passive"))
      (node (ref "U18") (pin "6") (pinfunction "VCC_6") (pintype "passive"))
    )
    (net (code "180") (name "unconnected-(U1-Q4-Pad14)") (class "Default")
      (node (ref "U1") (pin "14") (pinfunction "Q4_14") (pintype "passive"))
    )
    (net (code "181") (name "unconnected-(U1-Q5-Pad13)") (class "Default")
      (node (ref "U1") (pin "13") (pinfunction "Q5_13") (pintype "passive"))
    )
    (net (code "182") (name "unconnected-(U1-Q6-Pad12)") (class "Default")
      (node (ref "U1") (pin "12") (pinfunction "Q6_12") (pintype "passive"))
    )
    (net (code "183") (name "unconnected-(U1-Q7-Pad11)") (class "Default")
      (node (ref "U1") (pin "11") (pinfunction "Q7_11") (pintype "passive"))
    )
    (net (code "184") (name "unconnected-(U1-QS2-Pad10)") (class "Default")
      (node (ref "U1") (pin "10") (pinfunction "QS2_10") (pintype "passive"))
    )
    (net (code "185") (name "unconnected-(U2-Q4-Pad14)") (class "Default")
      (node (ref "U2") (pin "14") (pinfunction "Q4_14") (pintype "passive"))
    )
    (net (code "186") (name "unconnected-(U2-Q5-Pad13)") (class "Default")
      (node (ref "U2") (pin "13") (pinfunction "Q5_13") (pintype "passive"))
    )
    (net (code "187") (name "unconnected-(U2-Q6-Pad12)") (class "Default")
      (node (ref "U2") (pin "12") (pinfunction "Q6_12") (pintype "passive"))
    )
    (net (code "188") (name "unconnected-(U2-Q7-Pad11)") (class "Default")
      (node (ref "U2") (pin "11") (pinfunction "Q7_11") (pintype "passive"))
    )
    (net (code "189") (name "unconnected-(U2-QS2-Pad10)") (class "Default")
      (node (ref "U2") (pin "10") (pinfunction "QS2_10") (pintype "passive"))
    )
    (net (code "190") (name "unconnected-(U3-Q4-Pad14)") (class "Default")
      (node (ref "U3") (pin "14") (pinfunction "Q4_14") (pintype "passive"))
    )
    (net (code "191") (name "unconnected-(U3-Q5-Pad13)") (class "Default")
      (node (ref "U3") (pin "13") (pinfunction "Q5_13") (pintype "passive"))
    )
    (net (code "192") (name "unconnected-(U3-Q6-Pad12)") (class "Default")
      (node (ref "U3") (pin "12") (pinfunction "Q6_12") (pintype "passive"))
    )
    (net (code "193") (name "unconnected-(U3-Q7-Pad11)") (class "Default")
      (node (ref "U3") (pin "11") (pinfunction "Q7_11") (pintype "passive"))
    )
    (net (code "194") (name "unconnected-(U3-QS2-Pad10)") (class "Default")
      (node (ref "U3") (pin "10") (pinfunction "QS2_10") (pintype "passive"))
    )
    (net (code "195") (name "unconnected-(U4-Q4-Pad14)") (class "Default")
      (node (ref "U4") (pin "14") (pinfunction "Q4_14") (pintype "passive"))
    )
    (net (code "196") (name "unconnected-(U4-Q5-Pad13)") (class "Default")
      (node (ref "U4") (pin "13") (pinfunction "Q5_13") (pintype "passive"))
    )
    (net (code "197") (name "unconnected-(U4-Q6-Pad12)") (class "Default")
      (node (ref "U4") (pin "12") (pinfunction "Q6_12") (pintype "passive"))
    )
    (net (code "198") (name "unconnected-(U4-Q7-Pad11)") (class "Default")
      (node (ref "U4") (pin "11") (pinfunction "Q7_11") (pintype "passive"))
    )
    (net (code "199") (name "unconnected-(U4-QS2-Pad10)") (class "Default")
      (node (ref "U4") (pin "10") (pinfunction "QS2_10") (pintype "passive"))
    )
    (net (code "200") (name "unconnected-(U5-Q4-Pad14)") (class "Default")
      (node (ref "U5") (pin "14") (pinfunction "Q4_14") (pintype "passive"))
    )
    (net (code "201") (name "unconnected-(U5-Q5-Pad13)") (class "Default")
      (node (ref "U5") (pin "13") (pinfunction "Q5_13") (pintype "passive"))
    )
    (net (code "202") (name "unconnected-(U5-Q6-Pad12)") (class "Default")
      (node (ref "U5") (pin "12") (pinfunction "Q6_12") (pintype "passive"))
    )
    (net (code "203") (name "unconnected-(U5-Q7-Pad11)") (class "Default")
      (node (ref "U5") (pin "11") (pinfunction "Q7_11") (pintype "passive"))
    )
    (net (code "204") (name "unconnected-(U5-QS2-Pad10)") (class "Default")
      (node (ref "U5") (pin "10") (pinfunction "QS2_10") (pintype "passive"))
    )
    (net (code "205") (name "unconnected-(U6-Q4-Pad14)") (class "Default")
      (node (ref "U6") (pin "14") (pinfunction "Q4_14") (pintype "passive"))
    )
    (net (code "206") (name "unconnected-(U6-Q5-Pad13)") (class "Default")
      (node (ref "U6") (pin "13") (pinfunction "Q5_13") (pintype "passive"))
    )
    (net (code "207") (name "unconnected-(U6-Q6-Pad12)") (class "Default")
      (node (ref "U6") (pin "12") (pinfunction "Q6_12") (pintype "passive"))
    )
    (net (code "208") (name "unconnected-(U6-Q7-Pad11)") (class "Default")
      (node (ref "U6") (pin "11") (pinfunction "Q7_11") (pintype "passive"))
    )
    (net (code "209") (name "unconnected-(U6-QS2-Pad10)") (class "Default")
      (node (ref "U6") (pin "10") (pinfunction "QS2_10") (pintype "passive"))
    )
    (net (code "210") (name "unconnected-(U7-Q4-Pad14)") (class "Default")
      (node (ref "U7") (pin "14") (pinfunction "Q4_14") (pintype "passive"))
    )
    (net (code "211") (name "unconnected-(U7-Q5-Pad13)") (class "Default")
      (node (ref "U7") (pin "13") (pinfunction "Q5_13") (pintype "passive"))
    )
    (net (code "212") (name "unconnected-(U7-Q6-Pad12)") (class "Default")
      (node (ref "U7") (pin "12") (pinfunction "Q6_12") (pintype "passive"))
    )
    (net (code "213") (name "unconnected-(U7-Q7-Pad11)") (class "Default")
      (node (ref "U7") (pin "11") (pinfunction "Q7_11") (pintype "passive"))
    )
    (net (code "214") (name "unconnected-(U7-QS2-Pad10)") (class "Default")
      (node (ref "U7") (pin "10") (pinfunction "QS2_10") (pintype "passive"))
    )
    (net (code "215") (name "unconnected-(U8-Q4-Pad14)") (class "Default")
      (node (ref "U8") (pin "14") (pinfunction "Q4_14") (pintype "passive"))
    )
    (net (code "216") (name "unconnected-(U8-Q5-Pad13)") (class "Default")
      (node (ref "U8") (pin "13") (pinfunction "Q5_13") (pintype "passive"))
    )
    (net (code "217") (name "unconnected-(U8-Q6-Pad12)") (class "Default")
      (node (ref "U8") (pin "12") (pinfunction "Q6_12") (pintype "passive"))
    )
    (net (code "218") (name "unconnected-(U8-Q7-Pad11)") (class "Default")
      (node (ref "U8") (pin "11") (pinfunction "Q7_11") (pintype "passive"))
    )
    (net (code "219") (name "unconnected-(U8-QS2-Pad10)") (class "Default")
      (node (ref "U8") (pin "10") (pinfunction "QS2_10") (pintype "passive"))
    )
    (net (code "220") (name "unconnected-(U9-Q4-Pad14)") (class "Default")
      (node (ref "U9") (pin "14") (pinfunction "Q4_14") (pintype "passive"))
    )
    (net (code "221") (name "unconnected-(U9-Q5-Pad13)") (class "Default")
      (node (ref "U9") (pin "13") (pinfunction "Q5_13") (pintype "passive"))
    )
    (net (code "222") (name "unconnected-(U9-Q6-Pad12)") (class "Default")
      (node (ref "U9") (pin "12") (pinfunction "Q6_12") (pintype "passive"))
    )
    (net (code "223") (name "unconnected-(U9-Q7-Pad11)") (class "Default")
      (node (ref "U9") (pin "11") (pinfunction "Q7_11") (pintype "passive"))
    )
    (net (code "224") (name "unconnected-(U9-QS2-Pad10)") (class "Default")
      (node (ref "U9") (pin "10") (pinfunction "QS2_10") (pintype "passive"))
    )
    (net (code "225") (name "unconnected-(U10-Q4-Pad14)") (class "Default")
      (node (ref "U10") (pin "14") (pinfunction "Q4_14") (pintype "passive"))
    )
    (net (code "226") (name "unconnected-(U10-Q5-Pad13)") (class "Default")
      (node (ref "U10") (pin "13") (pinfunction "Q5_13") (pintype "passive"))
    )
    (net (code "227") (name "unconnected-(U10-Q6-Pad12)") (class "Default")
      (node (ref "U10") (pin "12") (pinfunction "Q6_12") (pintype "passive"))
    )
    (net (code "228") (name "unconnected-(U10-Q7-Pad11)") (class "Default")
      (node (ref "U10") (pin "11") (pinfunction "Q7_11") (pintype "passive"))
    )
    (net (code "229") (name "unconnected-(U10-QS2-Pad10)") (class "Default")
      (node (ref "U10") (pin "10") (pinfunction "QS2_10") (pintype "passive"))
    )
    (net (code "230") (name "unconnected-(U11-Q4-Pad14)") (class "Default")
      (node (ref "U11") (pin "14") (pinfunction "Q4_14") (pintype "passive"))
    )
    (net (code "231") (name "unconnected-(U11-Q5-Pad13)") (class "Default")
      (node (ref "U11") (pin "13") (pinfunction "Q5_13") (pintype "passive"))
    )
    (net (code "232") (name "unconnected-(U11-Q6-Pad12)") (class "Default")
      (node (ref "U11") (pin "12") (pinfunction "Q6_12") (pintype "passive"))
    )
    (net (code "233") (name "unconnected-(U11-Q7-Pad11)") (class "Default")
      (node (ref "U11") (pin "11") (pinfunction "Q7_11") (pintype "passive"))
    )
    (net (code "234") (name "unconnected-(U11-QS2-Pad10)") (class "Default")
      (node (ref "U11") (pin "10") (pinfunction "QS2_10") (pintype "passive"))
    )
    (net (code "235") (name "unconnected-(U12-Q4-Pad14)") (class "Default")
      (node (ref "U12") (pin "14") (pinfunction "Q4_14") (pintype "passive"))
    )
    (net (code "236") (name "unconnected-(U12-Q5-Pad13)") (class "Default")
      (node (ref "U12") (pin "13") (pinfunction "Q5_13") (pintype "passive"))
    )
    (net (code "237") (name "unconnected-(U12-Q6-Pad12)") (class "Default")
      (node (ref "U12") (pin "12") (pinfunction "Q6_12") (pintype "passive"))
    )
    (net (code "238") (name "unconnected-(U12-Q7-Pad11)") (class "Default")
      (node (ref "U12") (pin "11") (pinfunction "Q7_11") (pintype "passive"))
    )
    (net (code "239") (name "unconnected-(U12-QS2-Pad10)") (class "Default")
      (node (ref "U12") (pin "10") (pinfunction "QS2_10") (pintype "passive"))
    )
    (net (code "240") (name "unconnected-(U13-Q4-Pad14)") (class "Default")
      (node (ref "U13") (pin "14") (pinfunction "Q4_14") (pintype "passive"))
    )
    (net (code "241") (name "unconnected-(U13-Q5-Pad13)") (class "Default")
      (node (ref "U13") (pin "13") (pinfunction "Q5_13") (pintype "passive"))
    )
    (net (code "242") (name "unconnected-(U13-Q6-Pad12)") (class "Default")
      (node (ref "U13") (pin "12") (pinfunction "Q6_12") (pintype "passive"))
    )
    (net (code "243") (name "unconnected-(U13-Q7-Pad11)") (class "Default")
      (node (ref "U13") (pin "11") (pinfunction "Q7_11") (pintype "passive"))
    )
    (net (code "244") (name "unconnected-(U13-QS2-Pad10)") (class "Default")
      (node (ref "U13") (pin "10") (pinfunction "QS2_10") (pintype "passive"))
    )
    (net (code "245") (name "unconnected-(U14-Q4-Pad14)") (class "Default")
      (node (ref "U14") (pin "14") (pinfunction "Q4_14") (pintype "passive"))
    )
    (net (code "246") (name "unconnected-(U14-Q5-Pad13)") (class "Default")
      (node (ref "U14") (pin "13") (pinfunction "Q5_13") (pintype "passive"))
    )
    (net (code "247") (name "unconnected-(U14-Q6-Pad12)") (class "Default")
      (node (ref "U14") (pin "12") (pinfunction "Q6_12") (pintype "passive"))
    )
    (net (code "248") (name "unconnected-(U14-Q7-Pad11)") (class "Default")
      (node (ref "U14") (pin "11") (pinfunction "Q7_11") (pintype "passive"))
    )
    (net (code "249") (name "unconnected-(U14-QS2-Pad10)") (class "Default")
      (node (ref "U14") (pin "10") (pinfunction "QS2_10") (pintype "passive"))
    )
    (net (code "250") (name "unconnected-(U15-Q4-Pad14)") (class "Default")
      (node (ref "U15") (pin "14") (pinfunction "Q4_14") (pintype "passive"))
    )
    (net (code "251") (name "unconnected-(U15-Q5-Pad13)") (class "Default")
      (node (ref "U15") (pin "13") (pinfunction "Q5_13") (pintype "passive"))
    )
    (net (code "252") (name "unconnected-(U15-Q6-Pad12)") (class "Default")
      (node (ref "U15") (pin "12") (pinfunction "Q6_12") (pintype "passive"))
    )
    (net (code "253") (name "unconnected-(U15-Q7-Pad11)") (class "Default")
      (node (ref "U15") (pin "11") (pinfunction "Q7_11") (pintype "passive"))
    )
    (net (code "254") (name "unconnected-(U15-QS2-Pad10)") (class "Default")
      (node (ref "U15") (pin "10") (pinfunction "QS2_10") (pintype "passive"))
    )
    (net (code "255") (name "unconnected-(U16-Q4-Pad14)") (class "Default")
      (node (ref "U16") (pin "14") (pinfunction "Q4_14") (pintype "passive"))
    )
    (net (code "256") (name "unconnected-(U16-Q5-Pad13)") (class "Default")
      (node (ref "U16") (pin "13") (pinfunction "Q5_13") (pintype "passive"))
    )
    (net (code "257") (name "unconnected-(U16-Q6-Pad12)") (class "Default")
      (node (ref "U16") (pin "12") (pinfunction "Q6_12") (pintype "passive"))
    )
    (net (code "258") (name "unconnected-(U16-Q7-Pad11)") (class "Default")
      (node (ref "U16") (pin "11") (pinfunction "Q7_11") (pintype "passive"))
    )
    (net (code "259") (name "unconnected-(U16-QS2-Pad10)") (class "Default")
      (node (ref "U16") (pin "10") (pinfunction "QS2_10") (pintype "passive"))
    )
    (net (code "260") (name "unconnected-(U17-QS1-Pad9)") (class "Default")
      (node (ref "U17") (pin "9") (pinfunction "QS1_9") (pintype "passive"))
    )
    (net (code "261") (name "unconnected-(U17-QS2-Pad10)") (class "Default")
      (node (ref "U17") (pin "10") (pinfunction "QS2_10") (pintype "passive"))
    )
  )
)
